# S7G7_footprint_simplified_w_ethernet_v1p.net
KiCad netlist of a schematic drawn in EAGLE
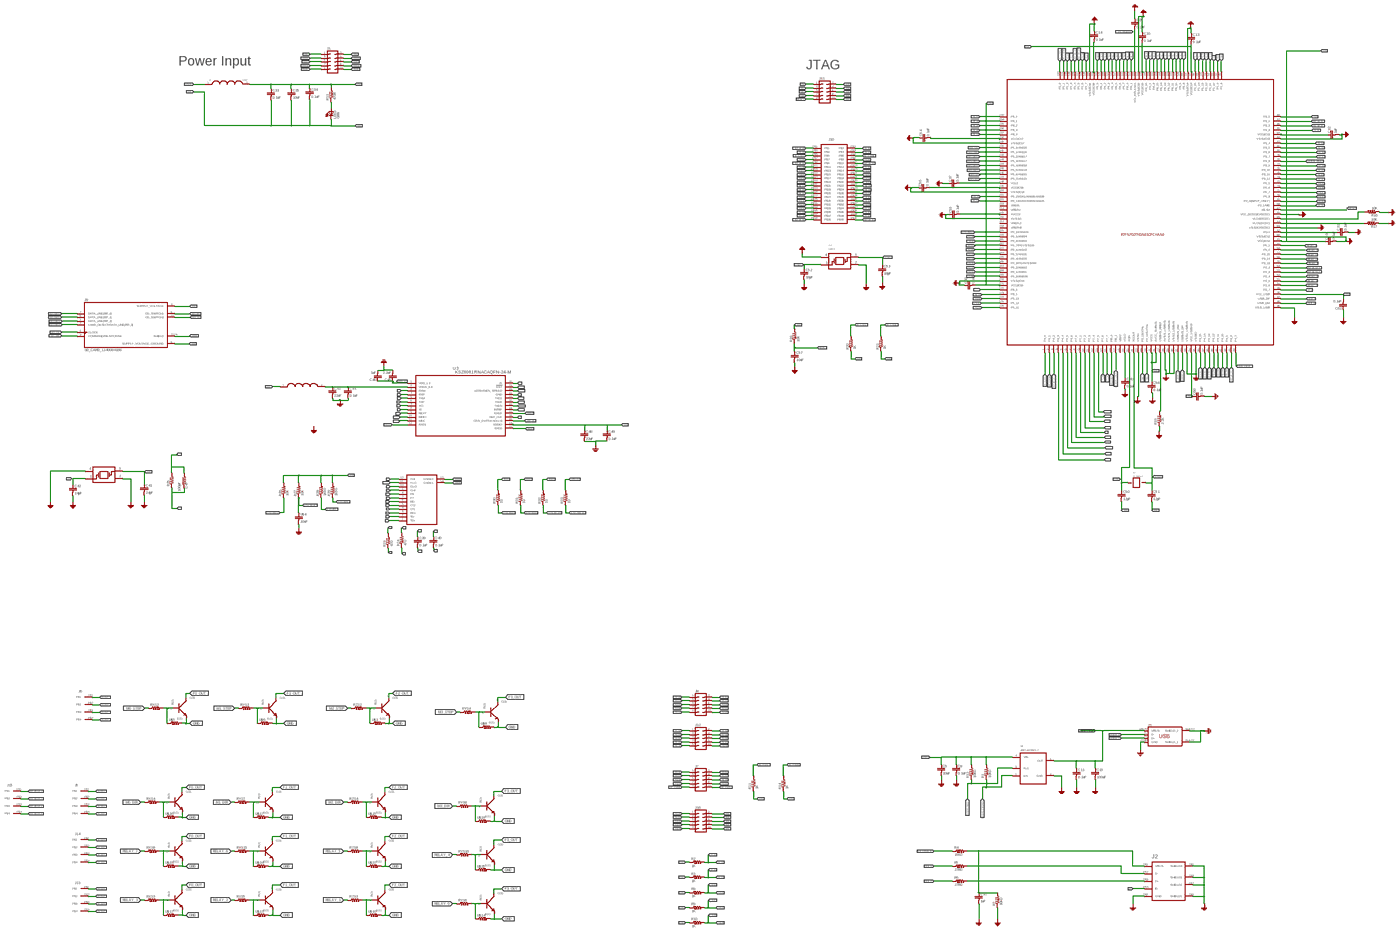
[diagram p0: schematic, sheet 1, overview]
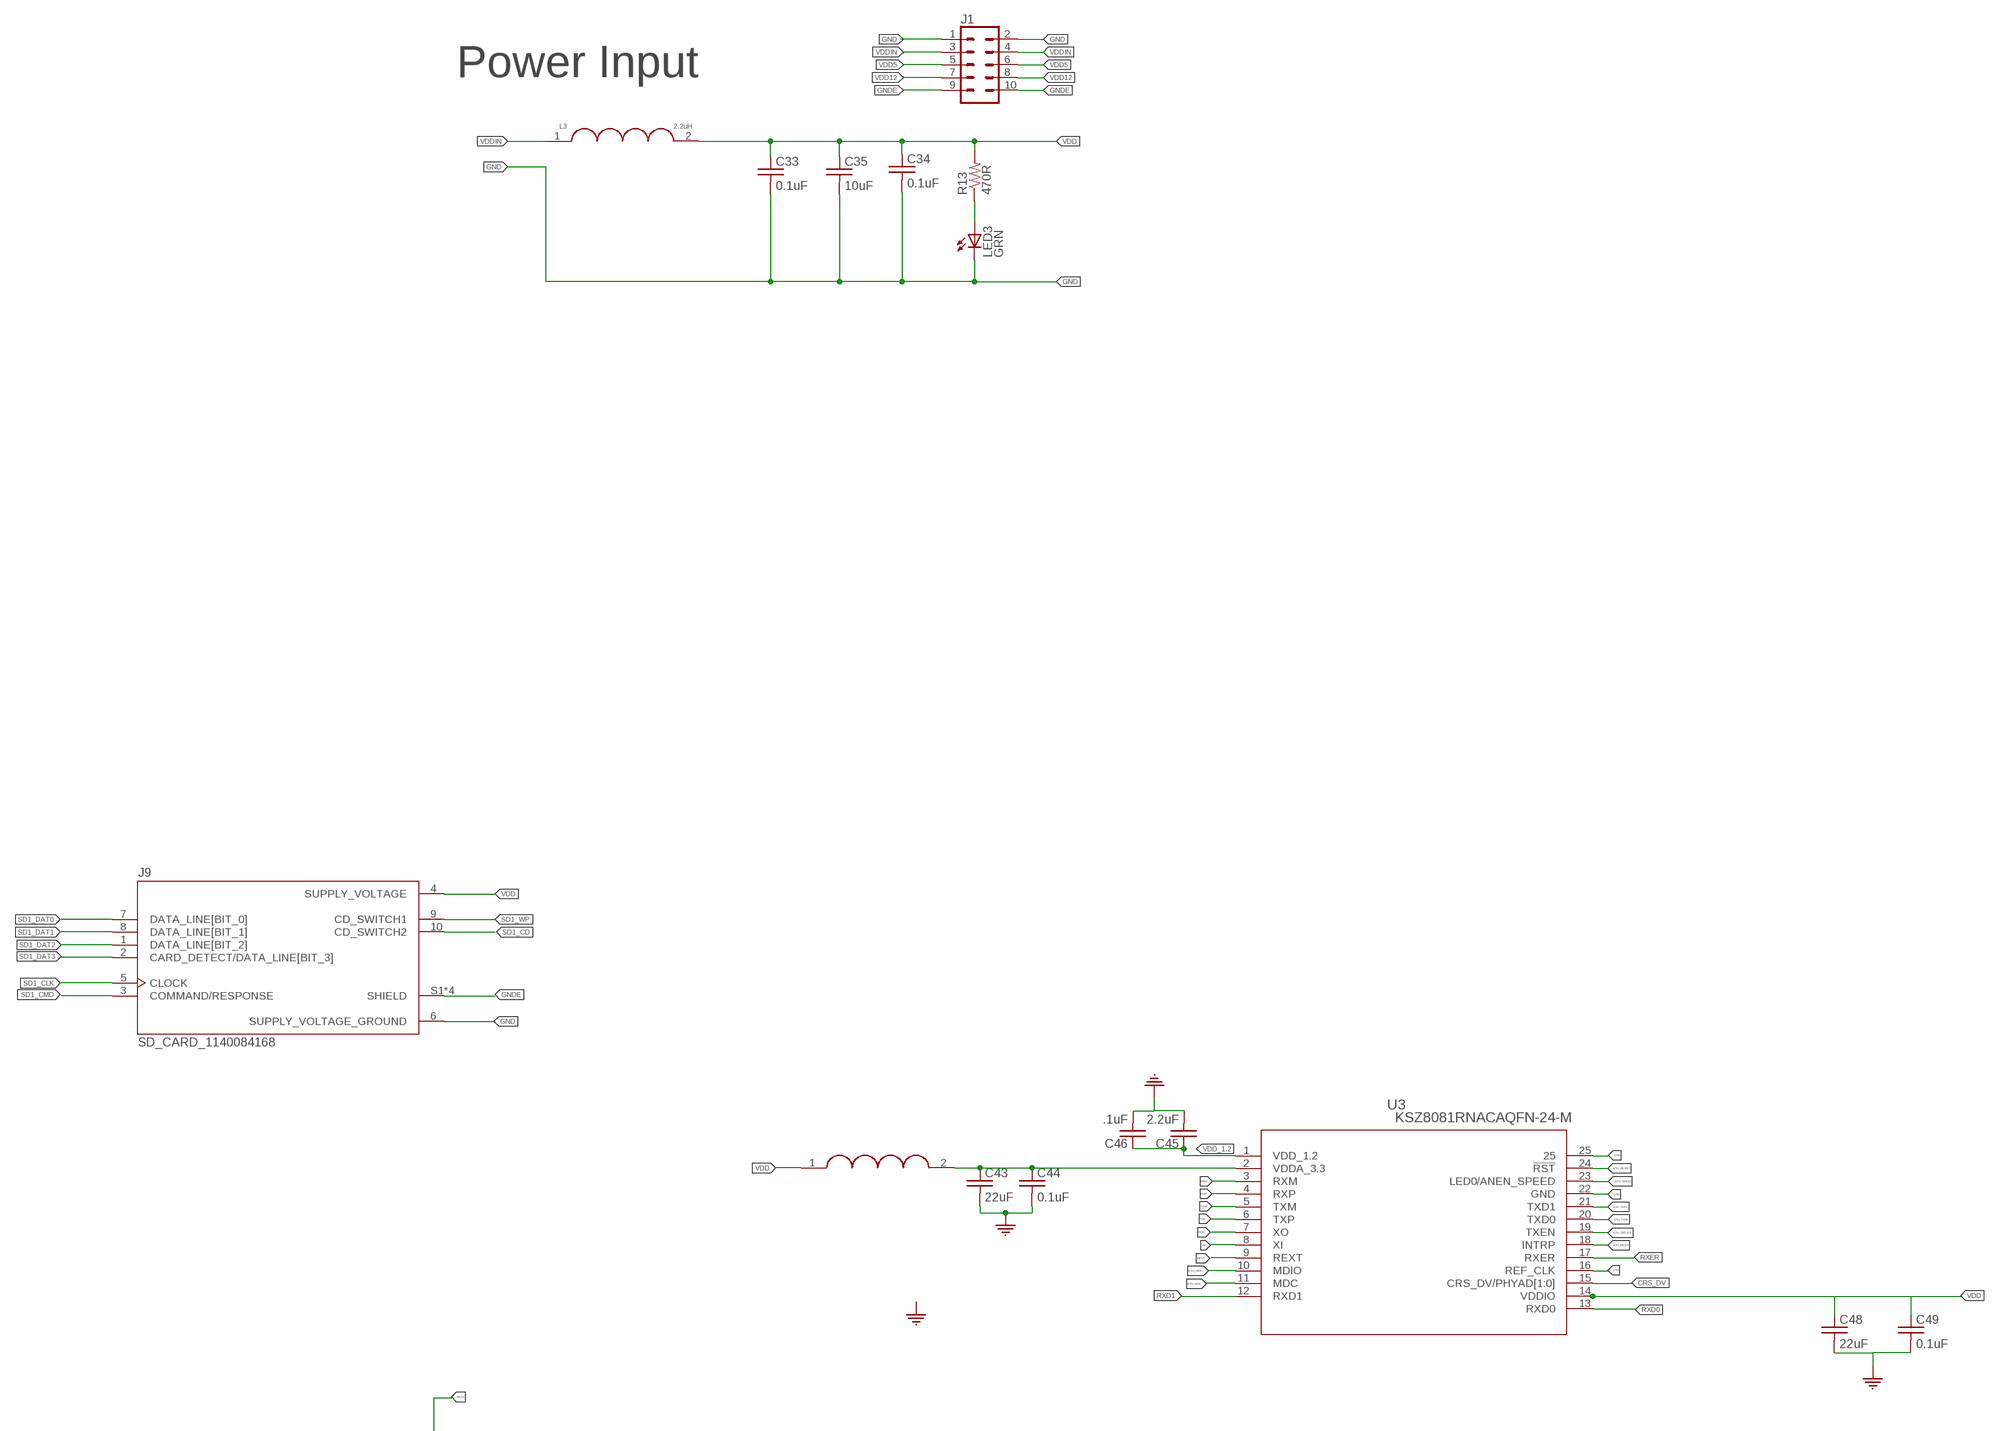
[diagram p1: schematic, sheet 1, part 1 of 4]
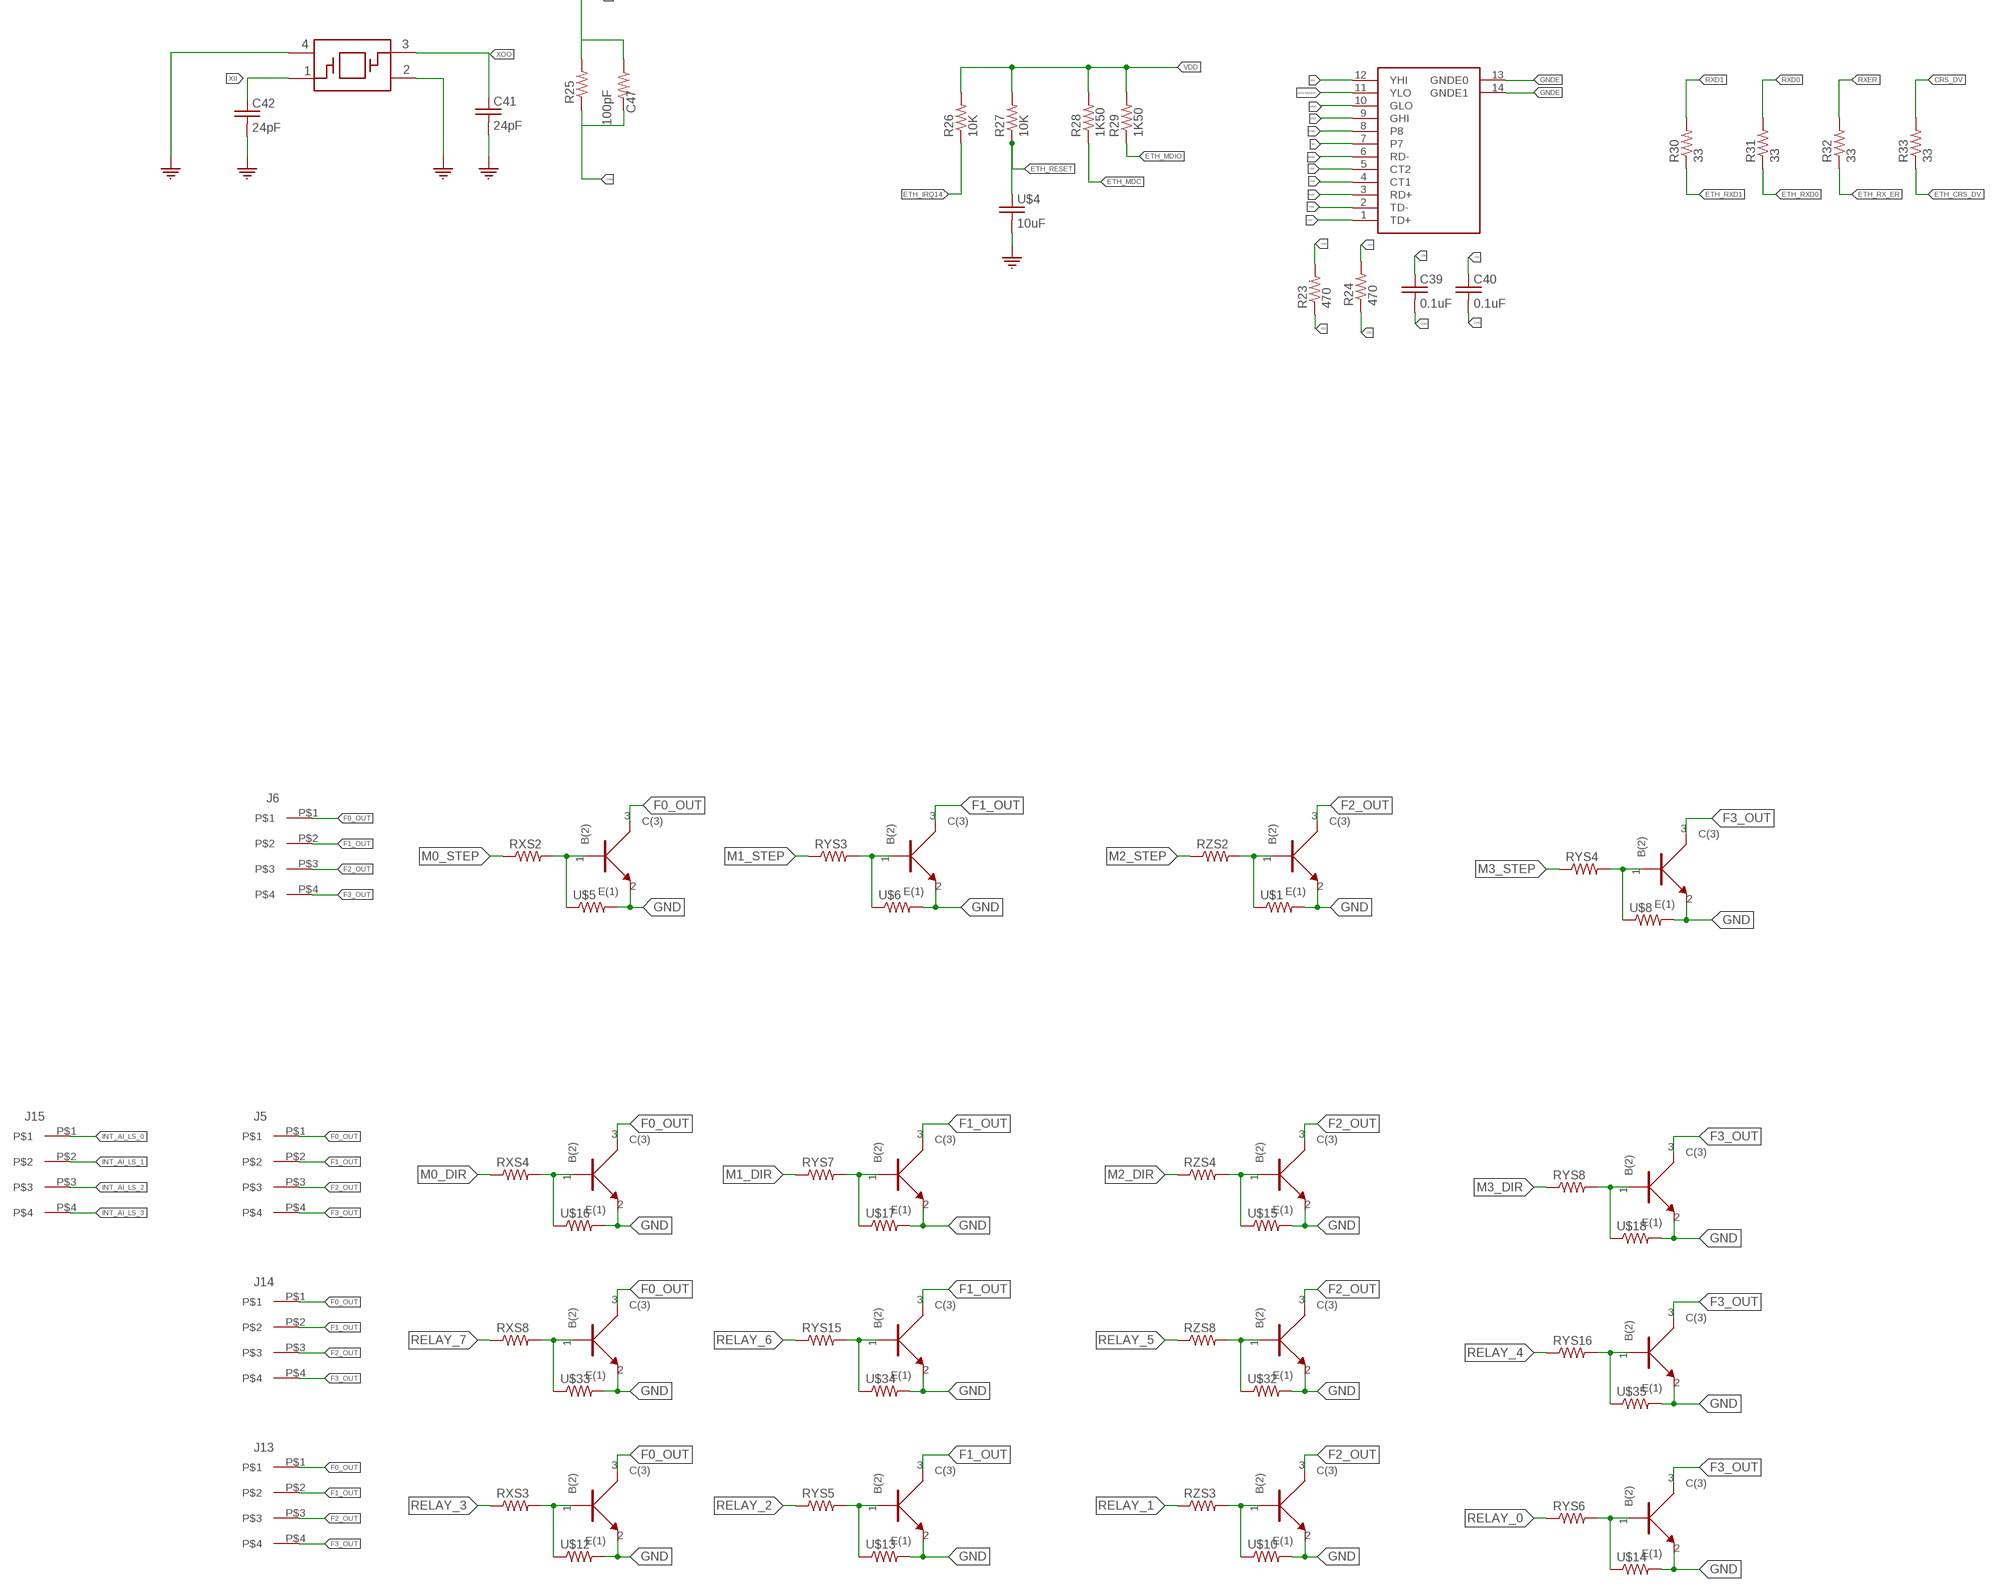
[diagram p2: schematic, sheet 1, part 2 of 4]
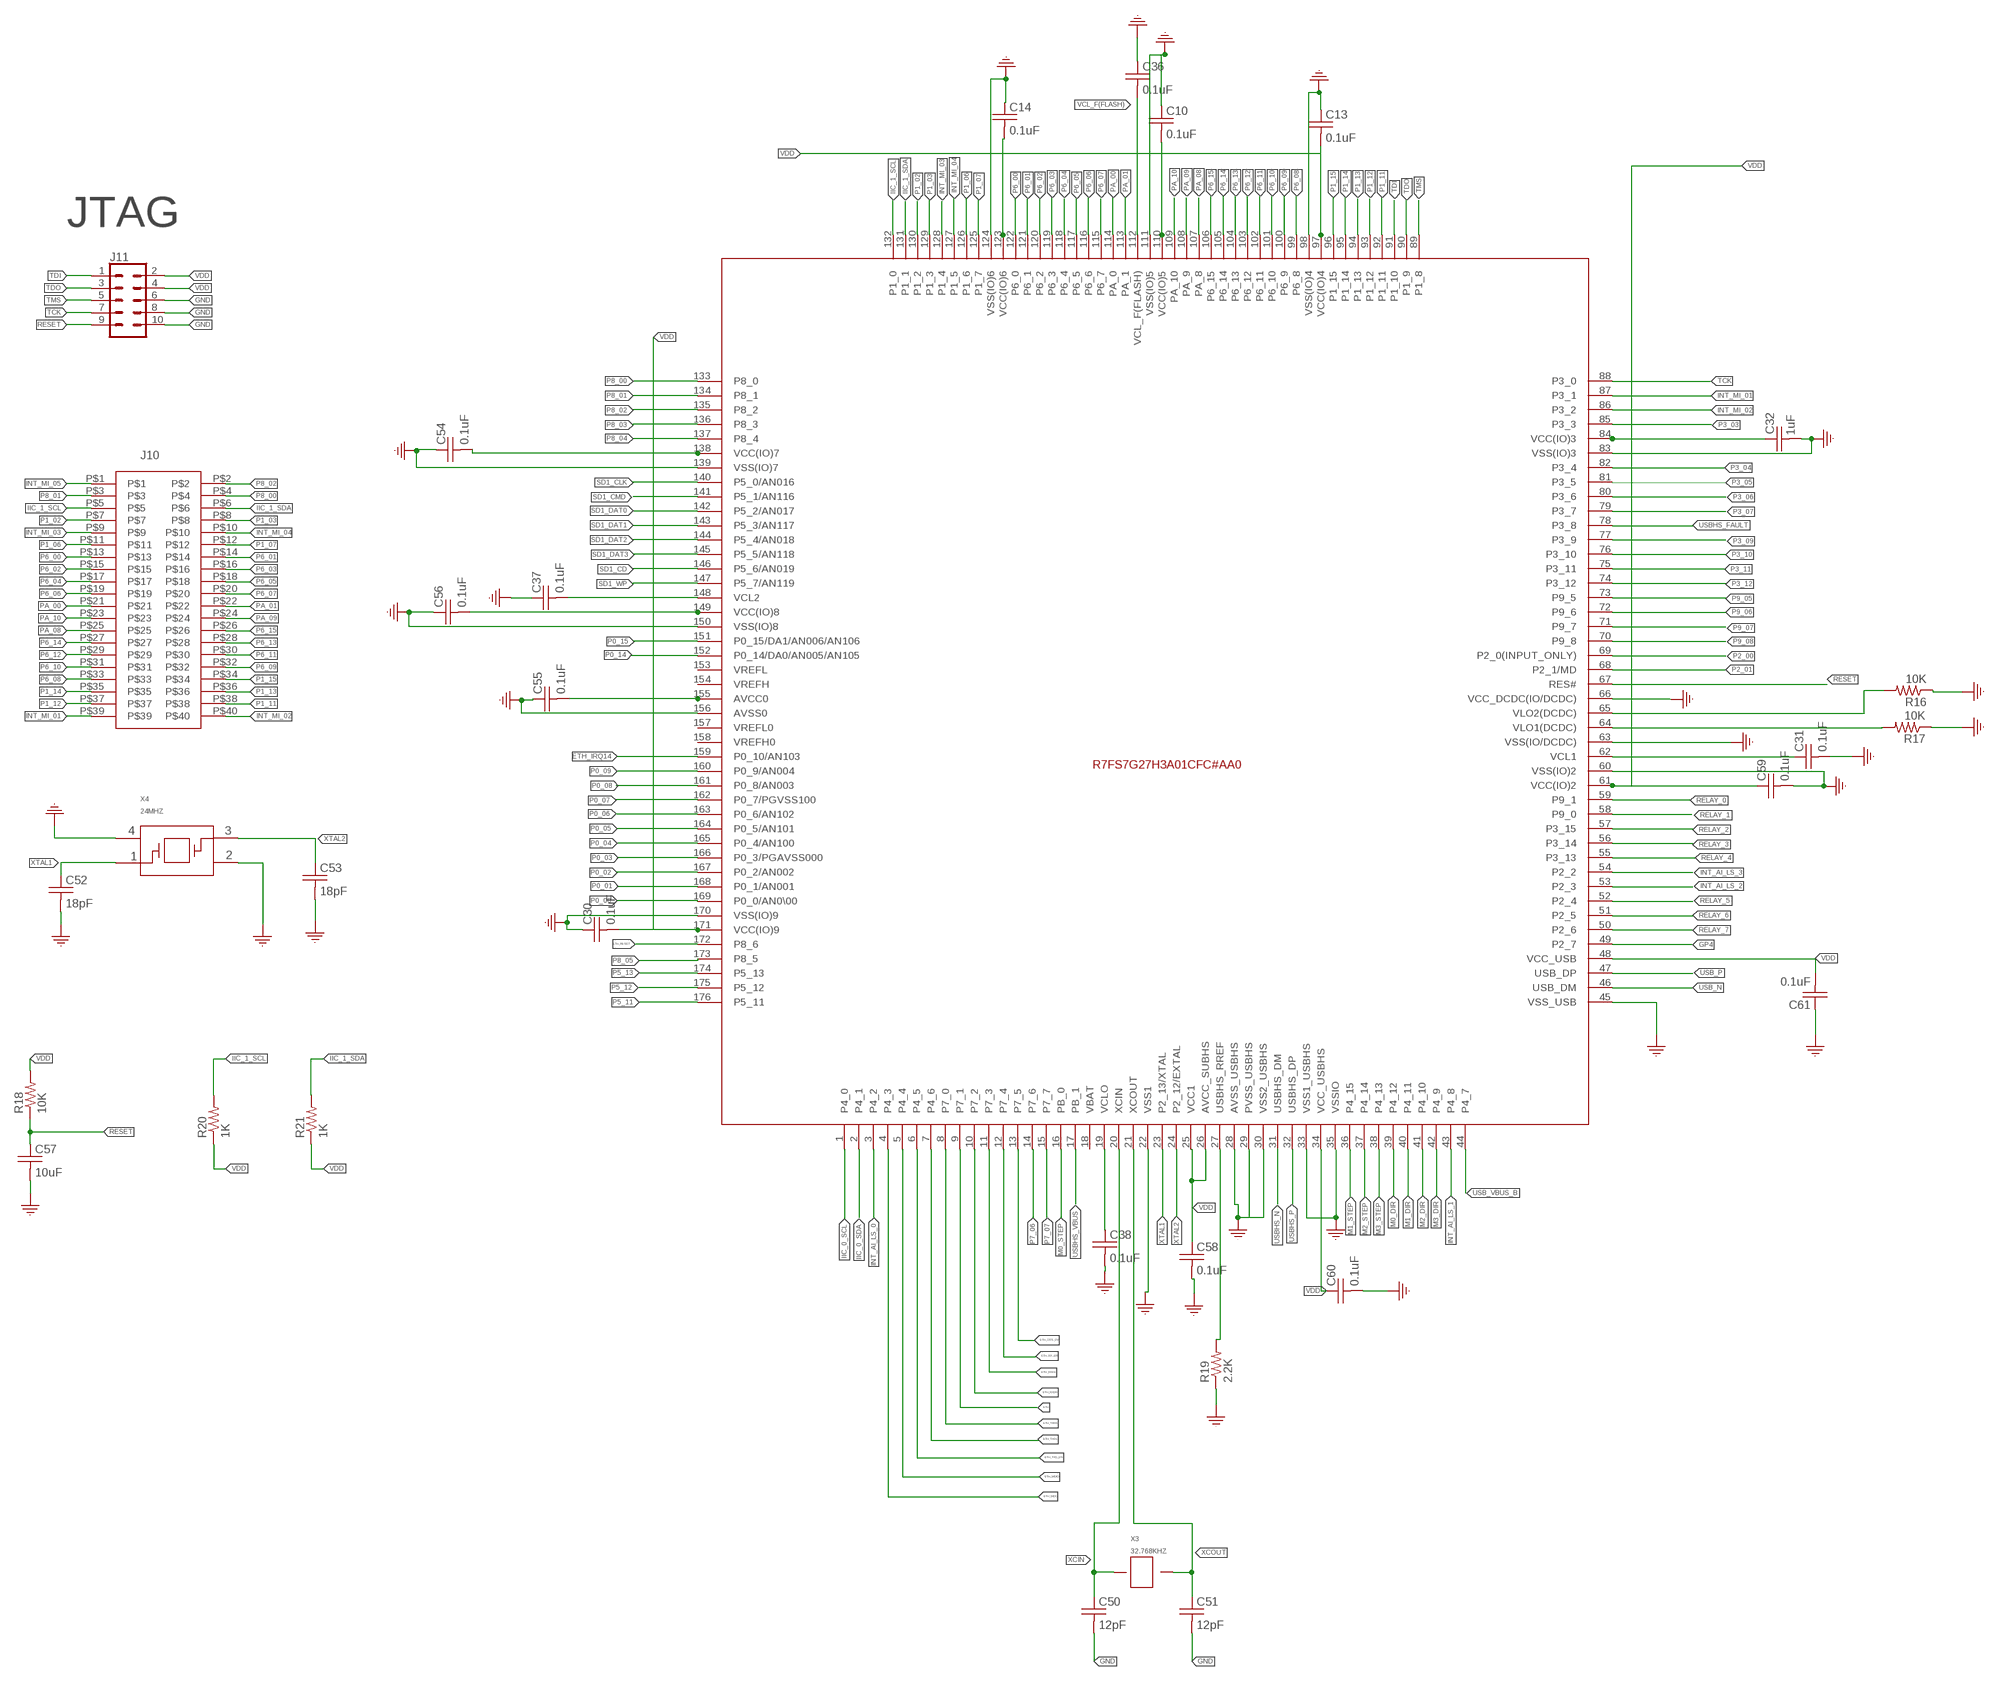
[diagram p3: schematic, sheet 1, part 3 of 4]
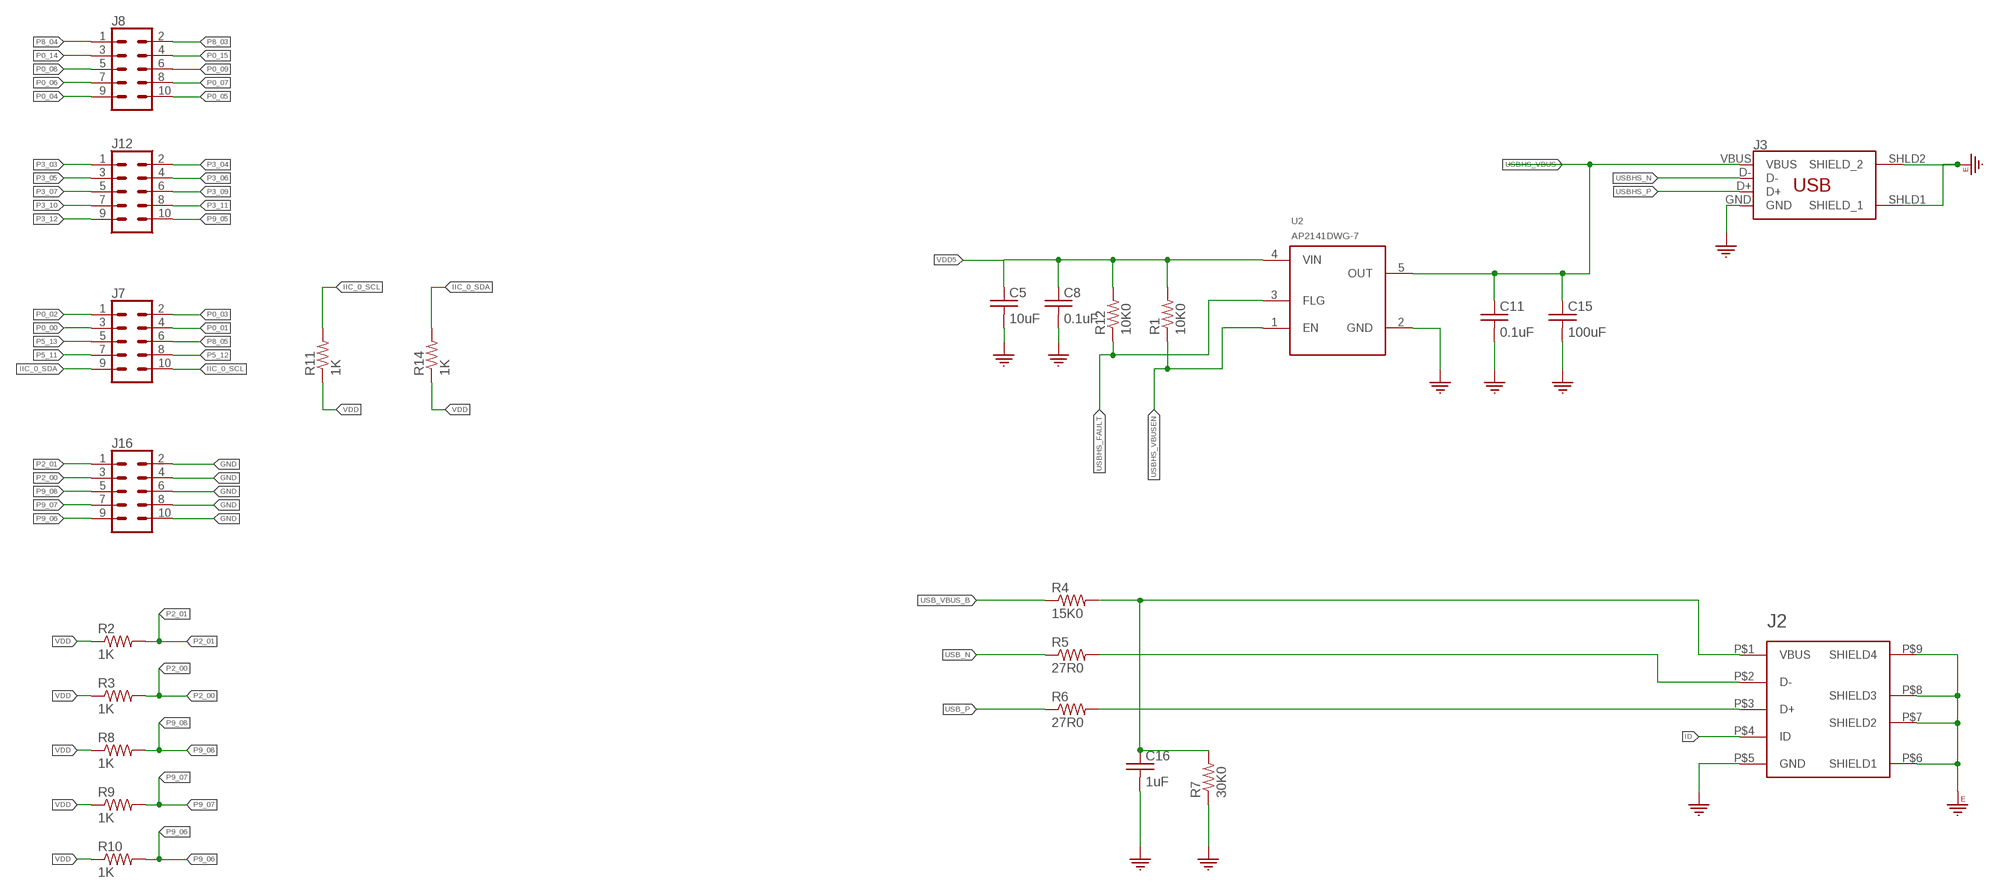
[diagram p4: schematic, sheet 1, part 4 of 4]

(export (version "E")
  (design (tool "Eeschema 10.0.6"))
  (components
    (comp (ref "C5")
      (value "10uF")
      (footprint "eagle-import:0402")
      (libsource (lib "eagle-import") (part "C_0402"))
    )
    (comp (ref "C8")
      (value "0.1uF")
      (footprint "eagle-import:0402")
      (libsource (lib "eagle-import") (part "C_0402"))
    )
    (comp (ref "C10")
      (value "0.1uF")
      (footprint "eagle-import:0402")
      (libsource (lib "eagle-import") (part "C_0402"))
    )
    (comp (ref "C11")
      (value "0.1uF")
      (footprint "eagle-import:0402")
      (libsource (lib "eagle-import") (part "C_0402"))
    )
    (comp (ref "C13")
      (value "0.1uF")
      (footprint "eagle-import:0402")
      (libsource (lib "eagle-import") (part "C_0402"))
    )
    (comp (ref "C14")
      (value "0.1uF")
      (footprint "eagle-import:0402")
      (libsource (lib "eagle-import") (part "C_0402"))
    )
    (comp (ref "C15")
      (value "100uF")
      (footprint "eagle-import:C1210")
      (libsource (lib "eagle-import") (part "C_1210"))
    )
    (comp (ref "C16")
      (value "1uF")
      (footprint "eagle-import:0402")
      (libsource (lib "eagle-import") (part "C_0402"))
    )
    (comp (ref "C30")
      (value "0.1uF")
      (footprint "eagle-import:0402")
      (libsource (lib "eagle-import") (part "C_0402"))
    )
    (comp (ref "C31")
      (value "0.1uF")
      (footprint "eagle-import:0402")
      (libsource (lib "eagle-import") (part "C_0402"))
    )
    (comp (ref "C32")
      (value "1uF")
      (footprint "eagle-import:0402")
      (libsource (lib "eagle-import") (part "C_0402"))
    )
    (comp (ref "C33")
      (value "0.1uF")
      (footprint "eagle-import:0402")
      (libsource (lib "eagle-import") (part "C_0402"))
    )
    (comp (ref "C34")
      (value "0.1uF")
      (footprint "eagle-import:0402")
      (libsource (lib "eagle-import") (part "C_0402"))
    )
    (comp (ref "C35")
      (value "10uF")
      (footprint "eagle-import:0402")
      (libsource (lib "eagle-import") (part "C_0402"))
    )
    (comp (ref "C36")
      (value "0.1uF")
      (footprint "eagle-import:0402")
      (libsource (lib "eagle-import") (part "C_0402"))
    )
    (comp (ref "C37")
      (value "0.1uF")
      (footprint "eagle-import:0402")
      (libsource (lib "eagle-import") (part "C_0402"))
    )
    (comp (ref "C38")
      (value "0.1uF")
      (footprint "eagle-import:0402")
      (libsource (lib "eagle-import") (part "C_0402"))
    )
    (comp (ref "C39")
      (value "0.1uF")
      (footprint "eagle-import:0402")
      (libsource (lib "eagle-import") (part "C_0402"))
    )
    (comp (ref "C40")
      (value "0.1uF")
      (footprint "eagle-import:0402")
      (libsource (lib "eagle-import") (part "C_0402"))
    )
    (comp (ref "C41")
      (value "24pF")
      (footprint "eagle-import:0402")
      (libsource (lib "eagle-import") (part "C_0402"))
    )
    (comp (ref "C42")
      (value "24pF")
      (footprint "eagle-import:0402")
      (libsource (lib "eagle-import") (part "C_0402"))
    )
    (comp (ref "C43")
      (value "22uF")
      (footprint "eagle-import:0603")
      (libsource (lib "eagle-import") (part "C_0603"))
    )
    (comp (ref "C44")
      (value "0.1uF")
      (footprint "eagle-import:0402")
      (libsource (lib "eagle-import") (part "C_0402"))
    )
    (comp (ref "C45")
      (value "2.2uF")
      (footprint "eagle-import:0402")
      (libsource (lib "eagle-import") (part "C_0402"))
    )
    (comp (ref "C46")
      (value ".1uF")
      (footprint "eagle-import:0402")
      (libsource (lib "eagle-import") (part "C_0402"))
    )
    (comp (ref "C47")
      (value "100pF")
      (footprint "eagle-import:0402")
      (libsource (lib "eagle-import") (part "R_0402"))
    )
    (comp (ref "C48")
      (value "22uF")
      (footprint "eagle-import:0603")
      (libsource (lib "eagle-import") (part "C_0603"))
    )
    (comp (ref "C49")
      (value "0.1uF")
      (footprint "eagle-import:0402")
      (libsource (lib "eagle-import") (part "C_0402"))
    )
    (comp (ref "C50")
      (value "12pF")
      (footprint "eagle-import:0402")
      (libsource (lib "eagle-import") (part "C_0402"))
    )
    (comp (ref "C51")
      (value "12pF")
      (footprint "eagle-import:0402")
      (libsource (lib "eagle-import") (part "C_0402"))
    )
    (comp (ref "C52")
      (value "18pF")
      (footprint "eagle-import:0402")
      (libsource (lib "eagle-import") (part "C_0402"))
    )
    (comp (ref "C53")
      (value "18pF")
      (footprint "eagle-import:0402")
      (libsource (lib "eagle-import") (part "C_0402"))
    )
    (comp (ref "C54")
      (value "0.1uF")
      (footprint "eagle-import:0402")
      (libsource (lib "eagle-import") (part "C_0402"))
    )
    (comp (ref "C55")
      (value "0.1uF")
      (footprint "eagle-import:0402")
      (libsource (lib "eagle-import") (part "C_0402"))
    )
    (comp (ref "C56")
      (value "0.1uF")
      (footprint "eagle-import:0402")
      (libsource (lib "eagle-import") (part "C_0402"))
    )
    (comp (ref "C57")
      (value "10uF")
      (footprint "eagle-import:0402")
      (libsource (lib "eagle-import") (part "C_0402"))
    )
    (comp (ref "C58")
      (value "0.1uF")
      (footprint "eagle-import:0402")
      (libsource (lib "eagle-import") (part "C_0402"))
    )
    (comp (ref "C59")
      (value "0.1uF")
      (footprint "eagle-import:0402")
      (libsource (lib "eagle-import") (part "C_0402"))
    )
    (comp (ref "C60")
      (value "0.1uF")
      (footprint "eagle-import:0402")
      (libsource (lib "eagle-import") (part "C_0402"))
    )
    (comp (ref "C61")
      (value "0.1uF")
      (footprint "eagle-import:0402")
      (libsource (lib "eagle-import") (part "C_0402"))
    )
    (comp (ref "FB2/2")
      (value "FB_0805_120_OHM")
      (footprint "eagle-import:0805")
      (libsource (lib "eagle-import") (part "FB_0805_120_OHM"))
    )
    (comp (ref "J1")
      (value "CONN_05X2PTH")
      (footprint "eagle-import:2X5")
      (libsource (lib "eagle-import") (part "CONN_05X2PTH"))
    )
    (comp (ref "J2")
      (value "USB_MICRO-B")
      (footprint "eagle-import:USB_MICRO-B")
      (libsource (lib "eagle-import") (part "USB_MICRO-B"))
    )
    (comp (ref "J3")
      (value "USB_A")
      (footprint "eagle-import:USB_A_SMT")
      (libsource (lib "eagle-import") (part "USB_A"))
    )
    (comp (ref "J4")
      (value "RJ45_WITH_ELEC")
      (footprint "eagle-import:RJ45_TH_ELEC")
      (libsource (lib "eagle-import") (part "RJ45_WITH_ELEC"))
    )
    (comp (ref "J5")
      (value "3.81MM_1_X_4_RT_ANGLE_PLUG_HEADER")
      (footprint "eagle-import:1X4_3.81MM_PITCH")
      (libsource (lib "eagle-import") (part "3.81MM_1_X_4_RT_ANGLE_PLUG_HEADER"))
    )
    (comp (ref "J6")
      (value "3.81MM_1_X_4_RT_ANGLE_PLUG_HEADER")
      (footprint "eagle-import:1X4_3.81MM_PITCH")
      (libsource (lib "eagle-import") (part "3.81MM_1_X_4_RT_ANGLE_PLUG_HEADER"))
    )
    (comp (ref "J7")
      (value "CONN_05X2NO_SILK")
      (footprint "eagle-import:2X5_NOSILK")
      (libsource (lib "eagle-import") (part "CONN_05X2NO_SILK"))
    )
    (comp (ref "J8")
      (value "CONN_05X2NO_SILK")
      (footprint "eagle-import:2X5_NOSILK")
      (libsource (lib "eagle-import") (part "CONN_05X2NO_SILK"))
    )
    (comp (ref "J9")
      (value "SD_CARD_1140084168")
      (footprint "eagle-import:AMPHENOL_1140084168")
      (fields
        (field (name "DIGI-KEY_PART_NUMBER") "114-00841-68-1-ND")
        (field (name "MF") "Amphenol ICC")
        (field (name "MP") "114-00841-68")
      )
      (libsource (lib "eagle-import") (part "SD_CARD_1140084168"))
    )
    (comp (ref "J10")
      (value "HEADER_2_X_20_GENERIC")
      (footprint "eagle-import:HEADER_2_X_20_.1_INCH")
      (libsource (lib "eagle-import") (part "HEADER_2_X_20_GENERIC"))
    )
    (comp (ref "J11")
      (value "CONN_05X2PTH")
      (footprint "eagle-import:2X5")
      (libsource (lib "eagle-import") (part "CONN_05X2PTH"))
    )
    (comp (ref "J12")
      (value "CONN_05X2NO_SILK")
      (footprint "eagle-import:2X5_NOSILK")
      (libsource (lib "eagle-import") (part "CONN_05X2NO_SILK"))
    )
    (comp (ref "J13")
      (value "3.81MM_1_X_4_RT_ANGLE_PLUG_HEADER")
      (footprint "eagle-import:1X4_3.81MM_PITCH")
      (libsource (lib "eagle-import") (part "3.81MM_1_X_4_RT_ANGLE_PLUG_HEADER"))
    )
    (comp (ref "J14")
      (value "3.81MM_1_X_4_RT_ANGLE_PLUG_HEADER")
      (footprint "eagle-import:1X4_3.81MM_PITCH")
      (libsource (lib "eagle-import") (part "3.81MM_1_X_4_RT_ANGLE_PLUG_HEADER"))
    )
    (comp (ref "J15")
      (value "3.81MM_1_X_4_RT_ANGLE_PLUG_HEADER")
      (footprint "eagle-import:1X4_3.81MM_PITCH")
      (libsource (lib "eagle-import") (part "3.81MM_1_X_4_RT_ANGLE_PLUG_HEADER"))
    )
    (comp (ref "J16")
      (value "CONN_05X2SHD_SMD")
      (footprint "eagle-import:2X5-SHROUDED_SMD")
      (libsource (lib "eagle-import") (part "CONN_05X2SHD_SMD"))
    )
    (comp (ref "L3")
      (value "2.2uH")
      (footprint "eagle-import:1008_(2520_METRIC)")
      (libsource (lib "eagle-import") (part "INDUCTOR_1008_2.2_MH_1.3A"))
    )
    (comp (ref "LED3")
      (value "LED_0805_GREEN")
      (footprint "eagle-import:LED_0805_GREEN")
      (libsource (lib "eagle-import") (part "LED_0805_GREEN"))
    )
    (comp (ref "R1")
      (value "10K0")
      (footprint "eagle-import:0402")
      (libsource (lib "eagle-import") (part "R_0402"))
    )
    (comp (ref "R2")
      (value "1K")
      (footprint "eagle-import:0402")
      (libsource (lib "eagle-import") (part "R_0402"))
    )
    (comp (ref "R3")
      (value "1K")
      (footprint "eagle-import:0402")
      (libsource (lib "eagle-import") (part "R_0402"))
    )
    (comp (ref "R4")
      (value "15K0")
      (footprint "eagle-import:0402")
      (libsource (lib "eagle-import") (part "R_0402"))
    )
    (comp (ref "R5")
      (value "27R0")
      (footprint "eagle-import:0402")
      (libsource (lib "eagle-import") (part "R_0402"))
    )
    (comp (ref "R6")
      (value "27R0")
      (footprint "eagle-import:0402")
      (libsource (lib "eagle-import") (part "R_0402"))
    )
    (comp (ref "R7")
      (value "30K0")
      (footprint "eagle-import:0402")
      (libsource (lib "eagle-import") (part "R_0402"))
    )
    (comp (ref "R8")
      (value "1K")
      (footprint "eagle-import:0402")
      (libsource (lib "eagle-import") (part "R_0402"))
    )
    (comp (ref "R9")
      (value "1K")
      (footprint "eagle-import:0402")
      (libsource (lib "eagle-import") (part "R_0402"))
    )
    (comp (ref "R10")
      (value "1K")
      (footprint "eagle-import:0402")
      (libsource (lib "eagle-import") (part "R_0402"))
    )
    (comp (ref "R11")
      (value "1K")
      (footprint "eagle-import:0402")
      (libsource (lib "eagle-import") (part "R_0402"))
    )
    (comp (ref "R12")
      (value "10K0")
      (footprint "eagle-import:0402")
      (libsource (lib "eagle-import") (part "R_0402"))
    )
    (comp (ref "R13")
      (value "470R")
      (footprint "eagle-import:0402")
      (libsource (lib "eagle-import") (part "R_0402"))
    )
    (comp (ref "R14")
      (value "1K")
      (footprint "eagle-import:0402")
      (libsource (lib "eagle-import") (part "R_0402"))
    )
    (comp (ref "R16")
      (value "10K")
      (footprint "eagle-import:0402")
      (libsource (lib "eagle-import") (part "R_0402"))
    )
    (comp (ref "R17")
      (value "10K")
      (footprint "eagle-import:0402")
      (libsource (lib "eagle-import") (part "R_0402"))
    )
    (comp (ref "R18")
      (value "10K")
      (footprint "eagle-import:0402")
      (libsource (lib "eagle-import") (part "R_0402"))
    )
    (comp (ref "R19")
      (value "2.2K")
      (footprint "eagle-import:0402")
      (libsource (lib "eagle-import") (part "R_0402"))
    )
    (comp (ref "R20")
      (value "1K")
      (footprint "eagle-import:0402")
      (libsource (lib "eagle-import") (part "R_0402"))
    )
    (comp (ref "R21")
      (value "1K")
      (footprint "eagle-import:0402")
      (libsource (lib "eagle-import") (part "R_0402"))
    )
    (comp (ref "R23")
      (value "470")
      (footprint "eagle-import:0402")
      (libsource (lib "eagle-import") (part "R_0402"))
    )
    (comp (ref "R24")
      (value "470")
      (footprint "eagle-import:0402")
      (libsource (lib "eagle-import") (part "R_0402"))
    )
    (comp (ref "R25")
      (value "6k49")
      (footprint "eagle-import:0402")
      (libsource (lib "eagle-import") (part "R_0402"))
    )
    (comp (ref "R26")
      (value "10K")
      (footprint "eagle-import:0402")
      (libsource (lib "eagle-import") (part "R_0402"))
    )
    (comp (ref "R27")
      (value "10K")
      (footprint "eagle-import:0402")
      (libsource (lib "eagle-import") (part "R_0402"))
    )
    (comp (ref "R28")
      (value "1K50")
      (footprint "eagle-import:0402")
      (libsource (lib "eagle-import") (part "R_0402"))
    )
    (comp (ref "R29")
      (value "1K50")
      (footprint "eagle-import:0402")
      (libsource (lib "eagle-import") (part "R_0402"))
    )
    (comp (ref "R30")
      (value "33")
      (footprint "eagle-import:0402")
      (libsource (lib "eagle-import") (part "R_0402"))
    )
    (comp (ref "R31")
      (value "33")
      (footprint "eagle-import:0402")
      (libsource (lib "eagle-import") (part "R_0402"))
    )
    (comp (ref "R32")
      (value "33")
      (footprint "eagle-import:0402")
      (libsource (lib "eagle-import") (part "R_0402"))
    )
    (comp (ref "R33")
      (value "33")
      (footprint "eagle-import:0402")
      (libsource (lib "eagle-import") (part "R_0402"))
    )
    (comp (ref "RXS2")
      (value "1K")
      (footprint "eagle-import:0402")
      (libsource (lib "eagle-import") (part "R_0402"))
    )
    (comp (ref "RXS3")
      (value "1K")
      (footprint "eagle-import:0402")
      (libsource (lib "eagle-import") (part "R_0402"))
    )
    (comp (ref "RXS4")
      (value "1K")
      (footprint "eagle-import:0402")
      (libsource (lib "eagle-import") (part "R_0402"))
    )
    (comp (ref "RXS8")
      (value "1K")
      (footprint "eagle-import:0402")
      (libsource (lib "eagle-import") (part "R_0402"))
    )
    (comp (ref "RYS3")
      (value "1K")
      (footprint "eagle-import:0402")
      (libsource (lib "eagle-import") (part "R_0402"))
    )
    (comp (ref "RYS4")
      (value "1K")
      (footprint "eagle-import:0402")
      (libsource (lib "eagle-import") (part "R_0402"))
    )
    (comp (ref "RYS5")
      (value "1K")
      (footprint "eagle-import:0402")
      (libsource (lib "eagle-import") (part "R_0402"))
    )
    (comp (ref "RYS6")
      (value "1K")
      (footprint "eagle-import:0402")
      (libsource (lib "eagle-import") (part "R_0402"))
    )
    (comp (ref "RYS7")
      (value "1K")
      (footprint "eagle-import:0402")
      (libsource (lib "eagle-import") (part "R_0402"))
    )
    (comp (ref "RYS8")
      (value "1K")
      (footprint "eagle-import:0402")
      (libsource (lib "eagle-import") (part "R_0402"))
    )
    (comp (ref "RYS15")
      (value "1K")
      (footprint "eagle-import:0402")
      (libsource (lib "eagle-import") (part "R_0402"))
    )
    (comp (ref "RYS16")
      (value "1K")
      (footprint "eagle-import:0402")
      (libsource (lib "eagle-import") (part "R_0402"))
    )
    (comp (ref "RZS2")
      (value "1K")
      (footprint "eagle-import:0402")
      (libsource (lib "eagle-import") (part "R_0402"))
    )
    (comp (ref "RZS3")
      (value "1K")
      (footprint "eagle-import:0402")
      (libsource (lib "eagle-import") (part "R_0402"))
    )
    (comp (ref "RZS4")
      (value "1K")
      (footprint "eagle-import:0402")
      (libsource (lib "eagle-import") (part "R_0402"))
    )
    (comp (ref "RZS8")
      (value "1K")
      (footprint "eagle-import:0402")
      (libsource (lib "eagle-import") (part "R_0402"))
    )
    (comp (ref "U$1")
      (value "1K")
      (footprint "eagle-import:0402")
      (libsource (lib "eagle-import") (part "R_0402"))
    )
    (comp (ref "U$3")
      (value "XTAL_25_MHZ")
      (footprint "eagle-import:SMD_3225")
      (libsource (lib "eagle-import") (part "XTAL_25_MHZ"))
    )
    (comp (ref "U$4")
      (value "10uF")
      (footprint "eagle-import:0402")
      (libsource (lib "eagle-import") (part "C_0402"))
    )
    (comp (ref "U$5")
      (value "1K")
      (footprint "eagle-import:0402")
      (libsource (lib "eagle-import") (part "R_0402"))
    )
    (comp (ref "U$6")
      (value "1K")
      (footprint "eagle-import:0402")
      (libsource (lib "eagle-import") (part "R_0402"))
    )
    (comp (ref "U$8")
      (value "1K")
      (footprint "eagle-import:0402")
      (libsource (lib "eagle-import") (part "R_0402"))
    )
    (comp (ref "U$10")
      (value "1K")
      (footprint "eagle-import:0402")
      (libsource (lib "eagle-import") (part "R_0402"))
    )
    (comp (ref "U$12")
      (value "1K")
      (footprint "eagle-import:0402")
      (libsource (lib "eagle-import") (part "R_0402"))
    )
    (comp (ref "U$13")
      (value "1K")
      (footprint "eagle-import:0402")
      (libsource (lib "eagle-import") (part "R_0402"))
    )
    (comp (ref "U$14")
      (value "1K")
      (footprint "eagle-import:0402")
      (libsource (lib "eagle-import") (part "R_0402"))
    )
    (comp (ref "U$15")
      (value "1K")
      (footprint "eagle-import:0402")
      (libsource (lib "eagle-import") (part "R_0402"))
    )
    (comp (ref "U$16")
      (value "1K")
      (footprint "eagle-import:0402")
      (libsource (lib "eagle-import") (part "R_0402"))
    )
    (comp (ref "U$17")
      (value "1K")
      (footprint "eagle-import:0402")
      (libsource (lib "eagle-import") (part "R_0402"))
    )
    (comp (ref "U$18")
      (value "1K")
      (footprint "eagle-import:0402")
      (libsource (lib "eagle-import") (part "R_0402"))
    )
    (comp (ref "U$32")
      (value "1K")
      (footprint "eagle-import:0402")
      (libsource (lib "eagle-import") (part "R_0402"))
    )
    (comp (ref "U$33")
      (value "1K")
      (footprint "eagle-import:0402")
      (libsource (lib "eagle-import") (part "R_0402"))
    )
    (comp (ref "U$34")
      (value "1K")
      (footprint "eagle-import:0402")
      (libsource (lib "eagle-import") (part "R_0402"))
    )
    (comp (ref "U$35")
      (value "1K")
      (footprint "eagle-import:0402")
      (libsource (lib "eagle-import") (part "R_0402"))
    )
    (comp (ref "U2")
      (value "AP2141DWG-5")
      (footprint "eagle-import:SOT-23-5")
      (libsource (lib "eagle-import") (part "AP2141DWG-5"))
    )
    (comp (ref "U3")
      (value "KSZ8081RNACAQFN-24-M")
      (footprint "eagle-import:QFN-24-M")
      (fields (field (name "MANUFACTURER_PART_NUMBER") "KSZ8081RNACA"))
      (libsource (lib "eagle-import") (part "KSZ8081RNACAQFN-24-M"))
    )
    (comp (ref "U4")
      (value "S7G2_X_176")
      (footprint "eagle-import:LQFP176_24X24")
      (libsource (lib "eagle-import") (part "S7G2_X_176"))
    )
    (comp (ref "U7")
      (value "BC846BW")
      (footprint "eagle-import:SOT323")
      (libsource (lib "eagle-import") (part "BC846BW"))
    )
    (comp (ref "U8")
      (value "BC846BW")
      (footprint "eagle-import:SOT323")
      (libsource (lib "eagle-import") (part "BC846BW"))
    )
    (comp (ref "U9")
      (value "BC846BW")
      (footprint "eagle-import:SOT323")
      (libsource (lib "eagle-import") (part "BC846BW"))
    )
    (comp (ref "U10")
      (value "BC846BW")
      (footprint "eagle-import:SOT323")
      (libsource (lib "eagle-import") (part "BC846BW"))
    )
    (comp (ref "U12")
      (value "BC846BW")
      (footprint "eagle-import:SOT323")
      (libsource (lib "eagle-import") (part "BC846BW"))
    )
    (comp (ref "U13")
      (value "BC846BW")
      (footprint "eagle-import:SOT323")
      (libsource (lib "eagle-import") (part "BC846BW"))
    )
    (comp (ref "U14")
      (value "BC846BW")
      (footprint "eagle-import:SOT323")
      (libsource (lib "eagle-import") (part "BC846BW"))
    )
    (comp (ref "U15")
      (value "BC846BW")
      (footprint "eagle-import:SOT323")
      (libsource (lib "eagle-import") (part "BC846BW"))
    )
    (comp (ref "U16")
      (value "BC846BW")
      (footprint "eagle-import:SOT323")
      (libsource (lib "eagle-import") (part "BC846BW"))
    )
    (comp (ref "U17")
      (value "BC846BW")
      (footprint "eagle-import:SOT323")
      (libsource (lib "eagle-import") (part "BC846BW"))
    )
    (comp (ref "U18")
      (value "BC846BW")
      (footprint "eagle-import:SOT323")
      (libsource (lib "eagle-import") (part "BC846BW"))
    )
    (comp (ref "U19")
      (value "BC846BW")
      (footprint "eagle-import:SOT323")
      (libsource (lib "eagle-import") (part "BC846BW"))
    )
    (comp (ref "U32")
      (value "BC846BW")
      (footprint "eagle-import:SOT323")
      (libsource (lib "eagle-import") (part "BC846BW"))
    )
    (comp (ref "U33")
      (value "BC846BW")
      (footprint "eagle-import:SOT323")
      (libsource (lib "eagle-import") (part "BC846BW"))
    )
    (comp (ref "U34")
      (value "BC846BW")
      (footprint "eagle-import:SOT323")
      (libsource (lib "eagle-import") (part "BC846BW"))
    )
    (comp (ref "U35")
      (value "BC846BW")
      (footprint "eagle-import:SOT323")
      (libsource (lib "eagle-import") (part "BC846BW"))
    )
    (comp (ref "X3")
      (value "32.768KHZ")
      (footprint "eagle-import:SMD_X_2_PADS")
      (libsource (lib "eagle-import") (part "XTAL_32.768KHZ"))
    )
    (comp (ref "X4")
      (value "24MHZ")
      (footprint "eagle-import:SMD_3225")
      (libsource (lib "eagle-import") (part "XTAL_24_MHZ"))
    )
  )
  (nets
    (net (code "1") (name "C58") (class "Default")
      (node (ref "C39") (pin "P$1") (pinfunction "1_P$1") (pintype "passive"))
      (node (ref "J4") (pin "4") (pinfunction "CT1_4") (pintype "bidirectional"))
    )
    (net (code "2") (name "C60") (class "Default")
      (node (ref "C40") (pin "P$1") (pinfunction "1_P$1") (pintype "passive"))
      (node (ref "J4") (pin "5") (pinfunction "CT2_5") (pintype "bidirectional"))
    )
    (net (code "3") (name "CRS_DV") (class "Default")
      (node (ref "R33") (pin "P$2") (pinfunction "2_P$2") (pintype "passive"))
      (node (ref "U3") (pin "15") (pinfunction "CRS_DV/PHYAD[1:0]_15") (pintype "bidirectional"))
    )
    (net (code "4") (name "ETH") (class "Default")
      (node (ref "U3") (pin "16") (pinfunction "REF_CLK_16") (pintype "bidirectional"))
      (node (ref "U4") (pin "9") (pinfunction "P7_1_9") (pintype "bidirectional"))
    )
    (net (code "5") (name "ETH_CRS_DV") (class "Default")
      (node (ref "R33") (pin "P$1") (pinfunction "1_P$1") (pintype "passive"))
      (node (ref "U4") (pin "13") (pinfunction "P7_5_13") (pintype "bidirectional"))
    )
    (net (code "6") (name "ETH_IRQ14") (class "Default")
      (node (ref "R26") (pin "P$1") (pinfunction "1_P$1") (pintype "passive"))
      (node (ref "U3") (pin "18") (pinfunction "INTRP_18") (pintype "bidirectional"))
      (node (ref "U4") (pin "159") (pinfunction "P0_10/AN103_159") (pintype "bidirectional"))
    )
    (net (code "7") (name "ETH_MDC") (class "Default")
      (node (ref "R28") (pin "P$1") (pinfunction "1_P$1") (pintype "passive"))
      (node (ref "U3") (pin "11") (pinfunction "MDC_11") (pintype "input"))
      (node (ref "U4") (pin "4") (pinfunction "P4_3_4") (pintype "bidirectional"))
    )
    (net (code "8") (name "ETH_MDIO") (class "Default")
      (node (ref "R29") (pin "P$1") (pinfunction "1_P$1") (pintype "passive"))
      (node (ref "U3") (pin "10") (pinfunction "MDIO_10") (pintype "bidirectional"))
      (node (ref "U4") (pin "5") (pinfunction "P4_4_5") (pintype "bidirectional"))
    )
    (net (code "9") (name "ETH_RESET") (class "Default")
      (node (ref "R27") (pin "P$1") (pinfunction "1_P$1") (pintype "passive"))
      (node (ref "U$4") (pin "P$1") (pinfunction "1_P$1") (pintype "passive"))
      (node (ref "U3") (pin "24") (pinfunction "~{RST}_24") (pintype "input"))
      (node (ref "U4") (pin "172") (pinfunction "P8_6_172") (pintype "bidirectional"))
    )
    (net (code "10") (name "ETH_RXD0") (class "Default")
      (node (ref "R31") (pin "P$1") (pinfunction "1_P$1") (pintype "passive"))
      (node (ref "U4") (pin "10") (pinfunction "P7_2_10") (pintype "bidirectional"))
    )
    (net (code "11") (name "ETH_RXD1") (class "Default")
      (node (ref "R30") (pin "P$1") (pinfunction "1_P$1") (pintype "passive"))
      (node (ref "U4") (pin "11") (pinfunction "P7_3_11") (pintype "bidirectional"))
    )
    (net (code "12") (name "ETH_RX_ER") (class "Default")
      (node (ref "R32") (pin "P$1") (pinfunction "1_P$1") (pintype "passive"))
      (node (ref "U4") (pin "12") (pinfunction "P7_4_12") (pintype "bidirectional"))
    )
    (net (code "13") (name "ETH_TXD0") (class "Default")
      (node (ref "U3") (pin "20") (pinfunction "TXD0_20") (pintype "input"))
      (node (ref "U4") (pin "8") (pinfunction "P7_0_8") (pintype "bidirectional"))
    )
    (net (code "14") (name "ETH_TXD1") (class "Default")
      (node (ref "U3") (pin "21") (pinfunction "TXD1_21") (pintype "bidirectional"))
      (node (ref "U4") (pin "7") (pinfunction "P4_6_7") (pintype "bidirectional"))
    )
    (net (code "15") (name "ETH_TXD_EN") (class "Default")
      (node (ref "U3") (pin "19") (pinfunction "TXEN_19") (pintype "input"))
      (node (ref "U4") (pin "6") (pinfunction "P4_5_6") (pintype "bidirectional"))
    )
    (net (code "16") (name "F0_OUT") (class "Default")
      (node (ref "J13") (pin "P$1") (pinfunction "P$1_P$1") (pintype "bidirectional"))
      (node (ref "J14") (pin "P$1") (pinfunction "P$1_P$1") (pintype "bidirectional"))
      (node (ref "J5") (pin "P$1") (pinfunction "P$1_P$1") (pintype "bidirectional"))
      (node (ref "J6") (pin "P$1") (pinfunction "P$1_P$1") (pintype "bidirectional"))
      (node (ref "U13") (pin "3") (pinfunction "C(3)_3") (pintype "input"))
      (node (ref "U17") (pin "3") (pinfunction "C(3)_3") (pintype "input"))
      (node (ref "U33") (pin "3") (pinfunction "C(3)_3") (pintype "input"))
      (node (ref "U8") (pin "3") (pinfunction "C(3)_3") (pintype "input"))
    )
    (net (code "17") (name "F1_OUT") (class "Default")
      (node (ref "J13") (pin "P$2") (pinfunction "P$2_P$2") (pintype "bidirectional"))
      (node (ref "J14") (pin "P$2") (pinfunction "P$2_P$2") (pintype "bidirectional"))
      (node (ref "J5") (pin "P$2") (pinfunction "P$2_P$2") (pintype "bidirectional"))
      (node (ref "J6") (pin "P$2") (pinfunction "P$2_P$2") (pintype "bidirectional"))
      (node (ref "U14") (pin "3") (pinfunction "C(3)_3") (pintype "input"))
      (node (ref "U18") (pin "3") (pinfunction "C(3)_3") (pintype "input"))
      (node (ref "U34") (pin "3") (pinfunction "C(3)_3") (pintype "input"))
      (node (ref "U9") (pin "3") (pinfunction "C(3)_3") (pintype "input"))
    )
    (net (code "18") (name "F2_OUT") (class "Default")
      (node (ref "J13") (pin "P$3") (pinfunction "P$3_P$3") (pintype "bidirectional"))
      (node (ref "J14") (pin "P$3") (pinfunction "P$3_P$3") (pintype "bidirectional"))
      (node (ref "J5") (pin "P$3") (pinfunction "P$3_P$3") (pintype "bidirectional"))
      (node (ref "J6") (pin "P$3") (pinfunction "P$3_P$3") (pintype "bidirectional"))
      (node (ref "U12") (pin "3") (pinfunction "C(3)_3") (pintype "input"))
      (node (ref "U16") (pin "3") (pinfunction "C(3)_3") (pintype "input"))
      (node (ref "U32") (pin "3") (pinfunction "C(3)_3") (pintype "input"))
      (node (ref "U7") (pin "3") (pinfunction "C(3)_3") (pintype "input"))
    )
    (net (code "19") (name "F3_OUT") (class "Default")
      (node (ref "J13") (pin "P$4") (pinfunction "P$4_P$4") (pintype "bidirectional"))
      (node (ref "J14") (pin "P$4") (pinfunction "P$4_P$4") (pintype "bidirectional"))
      (node (ref "J5") (pin "P$4") (pinfunction "P$4_P$4") (pintype "bidirectional"))
      (node (ref "J6") (pin "P$4") (pinfunction "P$4_P$4") (pintype "bidirectional"))
      (node (ref "U10") (pin "3") (pinfunction "C(3)_3") (pintype "input"))
      (node (ref "U15") (pin "3") (pinfunction "C(3)_3") (pintype "input"))
      (node (ref "U19") (pin "3") (pinfunction "C(3)_3") (pintype "input"))
      (node (ref "U35") (pin "3") (pinfunction "C(3)_3") (pintype "input"))
    )
    (net (code "20") (name "GND") (class "Default")
      (node (ref "C10") (pin "P$1") (pinfunction "1_P$1") (pintype "passive"))
      (node (ref "C11") (pin "P$2") (pinfunction "2_P$2") (pintype "passive"))
      (node (ref "C13") (pin "P$1") (pinfunction "1_P$1") (pintype "passive"))
      (node (ref "C14") (pin "P$1") (pinfunction "1_P$1") (pintype "passive"))
      (node (ref "C15") (pin "2") (pinfunction "2_2") (pintype "passive"))
      (node (ref "C16") (pin "P$2") (pinfunction "2_P$2") (pintype "passive"))
      (node (ref "C30") (pin "P$1") (pinfunction "1_P$1") (pintype "passive"))
      (node (ref "C31") (pin "P$2") (pinfunction "2_P$2") (pintype "passive"))
      (node (ref "C32") (pin "P$2") (pinfunction "2_P$2") (pintype "passive"))
      (node (ref "C33") (pin "P$2") (pinfunction "2_P$2") (pintype "passive"))
      (node (ref "C34") (pin "P$2") (pinfunction "2_P$2") (pintype "passive"))
      (node (ref "C35") (pin "P$2") (pinfunction "2_P$2") (pintype "passive"))
      (node (ref "C36") (pin "P$1") (pinfunction "1_P$1") (pintype "passive"))
      (node (ref "C37") (pin "P$1") (pinfunction "1_P$1") (pintype "passive"))
      (node (ref "C38") (pin "P$2") (pinfunction "2_P$2") (pintype "passive"))
      (node (ref "C39") (pin "P$2") (pinfunction "2_P$2") (pintype "passive"))
      (node (ref "C40") (pin "P$2") (pinfunction "2_P$2") (pintype "passive"))
      (node (ref "C41") (pin "P$2") (pinfunction "2_P$2") (pintype "passive"))
      (node (ref "C42") (pin "P$2") (pinfunction "2_P$2") (pintype "passive"))
      (node (ref "C43") (pin "2") (pinfunction "2_2") (pintype "passive"))
      (node (ref "C44") (pin "P$2") (pinfunction "2_P$2") (pintype "passive"))
      (node (ref "C45") (pin "P$2") (pinfunction "2_P$2") (pintype "passive"))
      (node (ref "C46") (pin "P$2") (pinfunction "2_P$2") (pintype "passive"))
      (node (ref "C47") (pin "P$2") (pinfunction "2_P$2") (pintype "passive"))
      (node (ref "C48") (pin "2") (pinfunction "2_2") (pintype "passive"))
      (node (ref "C49") (pin "P$2") (pinfunction "2_P$2") (pintype "passive"))
      (node (ref "C5") (pin "P$2") (pinfunction "2_P$2") (pintype "passive"))
      (node (ref "C50") (pin "P$2") (pinfunction "2_P$2") (pintype "passive"))
      (node (ref "C51") (pin "P$2") (pinfunction "2_P$2") (pintype "passive"))
      (node (ref "C52") (pin "P$2") (pinfunction "2_P$2") (pintype "passive"))
      (node (ref "C53") (pin "P$2") (pinfunction "2_P$2") (pintype "passive"))
      (node (ref "C54") (pin "P$1") (pinfunction "1_P$1") (pintype "passive"))
      (node (ref "C55") (pin "P$1") (pinfunction "1_P$1") (pintype "passive"))
      (node (ref "C56") (pin "P$1") (pinfunction "1_P$1") (pintype "passive"))
      (node (ref "C57") (pin "P$2") (pinfunction "2_P$2") (pintype "passive"))
      (node (ref "C58") (pin "P$2") (pinfunction "2_P$2") (pintype "passive"))
      (node (ref "C59") (pin "P$2") (pinfunction "2_P$2") (pintype "passive"))
      (node (ref "C60") (pin "P$2") (pinfunction "2_P$2") (pintype "passive"))
      (node (ref "C61") (pin "P$1") (pinfunction "1_P$1") (pintype "passive"))
      (node (ref "C8") (pin "P$2") (pinfunction "2_P$2") (pintype "passive"))
      (node (ref "J1") (pin "1") (pinfunction "1_1") (pintype "passive"))
      (node (ref "J1") (pin "2") (pinfunction "2_2") (pintype "passive"))
      (node (ref "J11") (pin "10") (pinfunction "10_10") (pintype "passive"))
      (node (ref "J11") (pin "6") (pinfunction "6_6") (pintype "passive"))
      (node (ref "J11") (pin "8") (pinfunction "8_8") (pintype "passive"))
      (node (ref "J16") (pin "10") (pinfunction "10_10") (pintype "passive"))
      (node (ref "J16") (pin "2") (pinfunction "2_2") (pintype "passive"))
      (node (ref "J16") (pin "4") (pinfunction "4_4") (pintype "passive"))
      (node (ref "J16") (pin "6") (pinfunction "6_6") (pintype "passive"))
      (node (ref "J16") (pin "8") (pinfunction "8_8") (pintype "passive"))
      (node (ref "J2") (pin "P$5") (pinfunction "GND_P$5") (pintype "bidirectional"))
      (node (ref "J3") (pin "GND") (pinfunction "GND_GND") (pintype "power_in"))
      (node (ref "J4") (pin "10") (pinfunction "GLO_10") (pintype "bidirectional"))
      (node (ref "J4") (pin "8") (pinfunction "P8_8") (pintype "bidirectional"))
      (node (ref "J9") (pin "6") (pinfunction "SUPPLY_VOLTAGE_GROUND_6") (pintype "power_in"))
      (node (ref "LED3") (pin "C") (pinfunction "C_C") (pintype "passive"))
      (node (ref "R16") (pin "P$1") (pinfunction "1_P$1") (pintype "passive"))
      (node (ref "R17") (pin "P$1") (pinfunction "1_P$1") (pintype "passive"))
      (node (ref "R19") (pin "P$1") (pinfunction "1_P$1") (pintype "passive"))
      (node (ref "R25") (pin "P$1") (pinfunction "1_P$1") (pintype "passive"))
      (node (ref "R7") (pin "P$1") (pinfunction "1_P$1") (pintype "passive"))
      (node (ref "U$1") (pin "P$2") (pinfunction "2_P$2") (pintype "passive"))
      (node (ref "U$10") (pin "P$2") (pinfunction "2_P$2") (pintype "passive"))
      (node (ref "U$12") (pin "P$2") (pinfunction "2_P$2") (pintype "passive"))
      (node (ref "U$13") (pin "P$2") (pinfunction "2_P$2") (pintype "passive"))
      (node (ref "U$14") (pin "P$2") (pinfunction "2_P$2") (pintype "passive"))
      (node (ref "U$15") (pin "P$2") (pinfunction "2_P$2") (pintype "passive"))
      (node (ref "U$16") (pin "P$2") (pinfunction "2_P$2") (pintype "passive"))
      (node (ref "U$17") (pin "P$2") (pinfunction "2_P$2") (pintype "passive"))
      (node (ref "U$18") (pin "P$2") (pinfunction "2_P$2") (pintype "passive"))
      (node (ref "U$3") (pin "2") (pinfunction "2_2") (pintype "bidirectional"))
      (node (ref "U$3") (pin "4") (pinfunction "4_4") (pintype "bidirectional"))
      (node (ref "U$32") (pin "P$2") (pinfunction "2_P$2") (pintype "passive"))
      (node (ref "U$33") (pin "P$2") (pinfunction "2_P$2") (pintype "passive"))
      (node (ref "U$34") (pin "P$2") (pinfunction "2_P$2") (pintype "passive"))
      (node (ref "U$35") (pin "P$2") (pinfunction "2_P$2") (pintype "passive"))
      (node (ref "U$4") (pin "P$2") (pinfunction "2_P$2") (pintype "passive"))
      (node (ref "U$5") (pin "P$2") (pinfunction "2_P$2") (pintype "passive"))
      (node (ref "U$6") (pin "P$2") (pinfunction "2_P$2") (pintype "passive"))
      (node (ref "U$8") (pin "P$2") (pinfunction "2_P$2") (pintype "passive"))
      (node (ref "U10") (pin "2") (pinfunction "E(1)_2") (pintype "output"))
      (node (ref "U12") (pin "2") (pinfunction "E(1)_2") (pintype "output"))
      (node (ref "U13") (pin "2") (pinfunction "E(1)_2") (pintype "output"))
      (node (ref "U14") (pin "2") (pinfunction "E(1)_2") (pintype "output"))
      (node (ref "U15") (pin "2") (pinfunction "E(1)_2") (pintype "output"))
      (node (ref "U16") (pin "2") (pinfunction "E(1)_2") (pintype "output"))
      (node (ref "U17") (pin "2") (pinfunction "E(1)_2") (pintype "output"))
      (node (ref "U18") (pin "2") (pinfunction "E(1)_2") (pintype "output"))
      (node (ref "U19") (pin "2") (pinfunction "E(1)_2") (pintype "output"))
      (node (ref "U2") (pin "2") (pinfunction "GND_2") (pintype "input"))
      (node (ref "U3") (pin "22") (pinfunction "GND_22") (pintype "power_in"))
      (node (ref "U3") (pin "25") (pinfunction "25_25") (pintype "passive"))
      (node (ref "U32") (pin "2") (pinfunction "E(1)_2") (pintype "output"))
      (node (ref "U33") (pin "2") (pinfunction "E(1)_2") (pintype "output"))
      (node (ref "U34") (pin "2") (pinfunction "E(1)_2") (pintype "output"))
      (node (ref "U35") (pin "2") (pinfunction "E(1)_2") (pintype "output"))
      (node (ref "U4") (pin "111") (pinfunction "VSS(IO)5_111") (pintype "bidirectional"))
      (node (ref "U4") (pin "124") (pinfunction "VSS(IO)6_124") (pintype "bidirectional"))
      (node (ref "U4") (pin "139") (pinfunction "VSS(IO)7_139") (pintype "bidirectional"))
      (node (ref "U4") (pin "150") (pinfunction "VSS(IO)8_150") (pintype "bidirectional"))
      (node (ref "U4") (pin "156") (pinfunction "AVSS0_156") (pintype "bidirectional"))
      (node (ref "U4") (pin "170") (pinfunction "VSS(IO)9_170") (pintype "bidirectional"))
      (node (ref "U4") (pin "22") (pinfunction "VSS1_22") (pintype "bidirectional"))
      (node (ref "U4") (pin "28") (pinfunction "AVSS_USBHS_28") (pintype "bidirectional"))
      (node (ref "U4") (pin "29") (pinfunction "PVSS_USBHS_29") (pintype "bidirectional"))
      (node (ref "U4") (pin "30") (pinfunction "VSS2_USBHS_30") (pintype "bidirectional"))
      (node (ref "U4") (pin "33") (pinfunction "VSS1_USBHS_33") (pintype "bidirectional"))
      (node (ref "U4") (pin "35") (pinfunction "VSSIO_35") (pintype "bidirectional"))
      (node (ref "U4") (pin "45") (pinfunction "VSS_USB_45") (pintype "bidirectional"))
      (node (ref "U4") (pin "60") (pinfunction "VSS(IO)2_60") (pintype "bidirectional"))
      (node (ref "U4") (pin "63") (pinfunction "VSS(IO/DCDC)_63") (pintype "bidirectional"))
      (node (ref "U4") (pin "66") (pinfunction "VCC_DCDC(IO/DCDC)_66") (pintype "bidirectional"))
      (node (ref "U4") (pin "83") (pinfunction "VSS(IO)3_83") (pintype "bidirectional"))
      (node (ref "U4") (pin "98") (pinfunction "VSS(IO)4_98") (pintype "bidirectional"))
      (node (ref "U7") (pin "2") (pinfunction "E(1)_2") (pintype "output"))
      (node (ref "U8") (pin "2") (pinfunction "E(1)_2") (pintype "output"))
      (node (ref "U9") (pin "2") (pinfunction "E(1)_2") (pintype "output"))
      (node (ref "X4") (pin "2") (pinfunction "2_2") (pintype "bidirectional"))
      (node (ref "X4") (pin "4") (pinfunction "4_4") (pintype "bidirectional"))
    )
    (net (code "21") (name "GNDE") (class "Default")
      (node (ref "J1") (pin "10") (pinfunction "10_10") (pintype "passive"))
      (node (ref "J1") (pin "9") (pinfunction "9_9") (pintype "passive"))
      (node (ref "J2") (pin "P$6") (pinfunction "SHIELD1_P$6") (pintype "bidirectional"))
      (node (ref "J2") (pin "P$7") (pinfunction "SHIELD2_P$7") (pintype "bidirectional"))
      (node (ref "J2") (pin "P$8") (pinfunction "SHIELD3_P$8") (pintype "bidirectional"))
      (node (ref "J2") (pin "P$9") (pinfunction "SHIELD4_P$9") (pintype "bidirectional"))
      (node (ref "J3") (pin "SHLD1") (pinfunction "SHIELD_1_SHLD1") (pintype "bidirectional"))
      (node (ref "J3") (pin "SHLD2") (pinfunction "SHIELD_2_SHLD2") (pintype "bidirectional"))
      (node (ref "J4") (pin "13") (pinfunction "GNDE0_13") (pintype "bidirectional"))
      (node (ref "J4") (pin "14") (pinfunction "GNDE1_14") (pintype "bidirectional"))
      (node (ref "J9") (pin "S1") (pinfunction "SHIELD_S1") (pintype "passive"))
      (node (ref "J9") (pin "S2") (pinfunction "SHIELD_S2") (pintype "passive"))
      (node (ref "J9") (pin "S3") (pinfunction "SHIELD_S3") (pintype "passive"))
      (node (ref "J9") (pin "S4") (pinfunction "SHIELD_S4") (pintype "passive"))
    )
    (net (code "22") (name "GP4") (class "Default")
      (node (ref "U4") (pin "49") (pinfunction "P2_7_49") (pintype "bidirectional"))
    )
    (net (code "23") (name "ID") (class "Default")
      (node (ref "J2") (pin "P$4") (pinfunction "ID_P$4") (pintype "bidirectional"))
    )
    (net (code "24") (name "IIC_0_SCL") (class "Default")
      (node (ref "J7") (pin "10") (pinfunction "10_10") (pintype "passive"))
      (node (ref "R11") (pin "P$2") (pinfunction "2_P$2") (pintype "passive"))
      (node (ref "U4") (pin "1") (pinfunction "P4_0_1") (pintype "bidirectional"))
    )
    (net (code "25") (name "IIC_0_SDA") (class "Default")
      (node (ref "J7") (pin "9") (pinfunction "9_9") (pintype "passive"))
      (node (ref "R14") (pin "P$2") (pinfunction "2_P$2") (pintype "passive"))
      (node (ref "U4") (pin "2") (pinfunction "P4_1_2") (pintype "bidirectional"))
    )
    (net (code "26") (name "IIC_1_SCL") (class "Default")
      (node (ref "J10") (pin "P$5") (pinfunction "P$5_P$5") (pintype "bidirectional"))
      (node (ref "R20") (pin "P$2") (pinfunction "2_P$2") (pintype "passive"))
      (node (ref "U4") (pin "132") (pinfunction "P1_0_132") (pintype "bidirectional"))
    )
    (net (code "27") (name "IIC_1_SDA") (class "Default")
      (node (ref "J10") (pin "P$6") (pinfunction "P$6_P$6") (pintype "bidirectional"))
      (node (ref "R21") (pin "P$2") (pinfunction "2_P$2") (pintype "passive"))
      (node (ref "U4") (pin "131") (pinfunction "P1_1_131") (pintype "bidirectional"))
    )
    (net (code "28") (name "INT_AI_LS_0") (class "Default")
      (node (ref "J15") (pin "P$1") (pinfunction "P$1_P$1") (pintype "bidirectional"))
      (node (ref "U4") (pin "3") (pinfunction "P4_2_3") (pintype "bidirectional"))
    )
    (net (code "29") (name "INT_AI_LS_1") (class "Default")
      (node (ref "J15") (pin "P$2") (pinfunction "P$2_P$2") (pintype "bidirectional"))
      (node (ref "U4") (pin "43") (pinfunction "P4_8_43") (pintype "bidirectional"))
    )
    (net (code "30") (name "INT_AI_LS_2") (class "Default")
      (node (ref "J15") (pin "P$3") (pinfunction "P$3_P$3") (pintype "bidirectional"))
      (node (ref "U4") (pin "53") (pinfunction "P2_3_53") (pintype "bidirectional"))
    )
    (net (code "31") (name "INT_AI_LS_3") (class "Default")
      (node (ref "J15") (pin "P$4") (pinfunction "P$4_P$4") (pintype "bidirectional"))
      (node (ref "U4") (pin "54") (pinfunction "P2_2_54") (pintype "bidirectional"))
    )
    (net (code "32") (name "INT_MI_01") (class "Default")
      (node (ref "J10") (pin "P$39") (pinfunction "P$39_P$39") (pintype "bidirectional"))
      (node (ref "U4") (pin "87") (pinfunction "P3_1_87") (pintype "bidirectional"))
    )
    (net (code "33") (name "INT_MI_02") (class "Default")
      (node (ref "J10") (pin "P$40") (pinfunction "P$40_P$40") (pintype "bidirectional"))
      (node (ref "U4") (pin "86") (pinfunction "P3_2_86") (pintype "bidirectional"))
    )
    (net (code "34") (name "INT_MI_03") (class "Default")
      (node (ref "J10") (pin "P$9") (pinfunction "P$9_P$9") (pintype "bidirectional"))
      (node (ref "U4") (pin "128") (pinfunction "P1_4_128") (pintype "bidirectional"))
    )
    (net (code "35") (name "INT_MI_04") (class "Default")
      (node (ref "J10") (pin "P$10") (pinfunction "P$10_P$10") (pintype "bidirectional"))
      (node (ref "U4") (pin "127") (pinfunction "P1_5_127") (pintype "bidirectional"))
    )
    (net (code "36") (name "INT_MI_05") (class "Default")
      (node (ref "J10") (pin "P$1") (pinfunction "P$1_P$1") (pintype "bidirectional"))
    )
    (net (code "37") (name "LED1{slash}SPEED") (class "Default")
      (node (ref "J4") (pin "11") (pinfunction "YLO_11") (pintype "bidirectional"))
      (node (ref "U3") (pin "23") (pinfunction "LED0/ANEN_SPEED_23") (pintype "bidirectional"))
    )
    (net (code "38") (name "M0_DIR") (class "Default")
      (node (ref "RXS4") (pin "P$1") (pinfunction "1_P$1") (pintype "passive"))
      (node (ref "U4") (pin "39") (pinfunction "P4_12_39") (pintype "bidirectional"))
    )
    (net (code "39") (name "M0_STEP") (class "Default")
      (node (ref "RXS2") (pin "P$1") (pinfunction "1_P$1") (pintype "passive"))
      (node (ref "U4") (pin "16") (pinfunction "PB_0_16") (pintype "bidirectional"))
    )
    (net (code "40") (name "M1_DIR") (class "Default")
      (node (ref "RYS7") (pin "P$1") (pinfunction "1_P$1") (pintype "passive"))
      (node (ref "U4") (pin "40") (pinfunction "P4_11_40") (pintype "bidirectional"))
    )
    (net (code "41") (name "M1_STEP") (class "Default")
      (node (ref "RYS3") (pin "P$1") (pinfunction "1_P$1") (pintype "passive"))
      (node (ref "U4") (pin "36") (pinfunction "P4_15_36") (pintype "bidirectional"))
    )
    (net (code "42") (name "M2_DIR") (class "Default")
      (node (ref "RZS4") (pin "P$1") (pinfunction "1_P$1") (pintype "passive"))
      (node (ref "U4") (pin "41") (pinfunction "P4_10_41") (pintype "bidirectional"))
    )
    (net (code "43") (name "M2_STEP") (class "Default")
      (node (ref "RZS2") (pin "P$1") (pinfunction "1_P$1") (pintype "passive"))
      (node (ref "U4") (pin "37") (pinfunction "P4_14_37") (pintype "bidirectional"))
    )
    (net (code "44") (name "M3_DIR") (class "Default")
      (node (ref "RYS8") (pin "P$1") (pinfunction "1_P$1") (pintype "passive"))
      (node (ref "U4") (pin "42") (pinfunction "P4_9_42") (pintype "bidirectional"))
    )
    (net (code "45") (name "M3_STEP") (class "Default")
      (node (ref "RYS4") (pin "P$1") (pinfunction "1_P$1") (pintype "passive"))
      (node (ref "U4") (pin "38") (pinfunction "P4_13_38") (pintype "bidirectional"))
    )
    (net (code "46") (name "NC") (class "Default")
      (node (ref "J4") (pin "7") (pinfunction "P7_7") (pintype "bidirectional"))
    )
    (net (code "47") (name "Net-(C16-1)") (class "Default")
      (node (ref "C16") (pin "P$1") (pinfunction "1_P$1") (pintype "passive"))
      (node (ref "J2") (pin "P$1") (pinfunction "VBUS_P$1") (pintype "bidirectional"))
      (node (ref "R4") (pin "P$2") (pinfunction "2_P$2") (pintype "passive"))
      (node (ref "R7") (pin "P$2") (pinfunction "2_P$2") (pintype "passive"))
    )
    (net (code "48") (name "Net-(C31-1)") (class "Default")
      (node (ref "C31") (pin "P$1") (pinfunction "1_P$1") (pintype "passive"))
      (node (ref "U4") (pin "62") (pinfunction "VCL1_62") (pintype "bidirectional"))
    )
    (net (code "49") (name "Net-(C37-2)") (class "Default")
      (node (ref "C37") (pin "P$2") (pinfunction "2_P$2") (pintype "passive"))
      (node (ref "U4") (pin "148") (pinfunction "VCL2_148") (pintype "bidirectional"))
    )
    (net (code "50") (name "Net-(C38-1)") (class "Default")
      (node (ref "C38") (pin "P$1") (pinfunction "1_P$1") (pintype "passive"))
      (node (ref "U4") (pin "19") (pinfunction "VCLO_19") (pintype "bidirectional"))
    )
    (net (code "51") (name "Net-(C44-1)") (class "Default")
      (node (ref "C43") (pin "1") (pinfunction "1_1") (pintype "passive"))
      (node (ref "C44") (pin "P$1") (pinfunction "1_P$1") (pintype "passive"))
      (node (ref "FB2/2") (pin "2") (pinfunction "P$2_2") (pintype "bidirectional"))
      (node (ref "U3") (pin "2") (pinfunction "VDDA_3.3_2") (pintype "power_in"))
    )
    (net (code "52") (name "Net-(J2-D+)") (class "Default")
      (node (ref "J2") (pin "P$3") (pinfunction "D+_P$3") (pintype "bidirectional"))
      (node (ref "R6") (pin "P$2") (pinfunction "2_P$2") (pintype "passive"))
    )
    (net (code "53") (name "Net-(J2-D-)") (class "Default")
      (node (ref "J2") (pin "P$2") (pinfunction "D-_P$2") (pintype "bidirectional"))
      (node (ref "R5") (pin "P$2") (pinfunction "2_P$2") (pintype "passive"))
    )
    (net (code "54") (name "Net-(R13-1)") (class "Default")
      (node (ref "LED3") (pin "A") (pinfunction "A_A") (pintype "passive"))
      (node (ref "R13") (pin "P$1") (pinfunction "1_P$1") (pintype "passive"))
    )
    (net (code "55") (name "Net-(R16-2)") (class "Default")
      (node (ref "R16") (pin "P$2") (pinfunction "2_P$2") (pintype "passive"))
      (node (ref "U4") (pin "65") (pinfunction "VLO2(DCDC)_65") (pintype "bidirectional"))
    )
    (net (code "56") (name "Net-(R17-2)") (class "Default")
      (node (ref "R17") (pin "P$2") (pinfunction "2_P$2") (pintype "passive"))
      (node (ref "U4") (pin "64") (pinfunction "VLO1(DCDC)_64") (pintype "bidirectional"))
    )
    (net (code "57") (name "Net-(R19-2)") (class "Default")
      (node (ref "R19") (pin "P$2") (pinfunction "2_P$2") (pintype "passive"))
      (node (ref "U4") (pin "27") (pinfunction "USBHS_RREF_27") (pintype "bidirectional"))
    )
    (net (code "58") (name "Net-(RXS2-2)") (class "Default")
      (node (ref "RXS2") (pin "P$2") (pinfunction "2_P$2") (pintype "passive"))
      (node (ref "U$5") (pin "P$1") (pinfunction "1_P$1") (pintype "passive"))
      (node (ref "U8") (pin "1") (pinfunction "B(2)_1") (pintype "input"))
    )
    (net (code "59") (name "Net-(RXS3-2)") (class "Default")
      (node (ref "RXS3") (pin "P$2") (pinfunction "2_P$2") (pintype "passive"))
      (node (ref "U$12") (pin "P$1") (pinfunction "1_P$1") (pintype "passive"))
      (node (ref "U13") (pin "1") (pinfunction "B(2)_1") (pintype "input"))
    )
    (net (code "60") (name "Net-(RXS4-2)") (class "Default")
      (node (ref "RXS4") (pin "P$2") (pinfunction "2_P$2") (pintype "passive"))
      (node (ref "U$16") (pin "P$1") (pinfunction "1_P$1") (pintype "passive"))
      (node (ref "U17") (pin "1") (pinfunction "B(2)_1") (pintype "input"))
    )
    (net (code "61") (name "Net-(RXS8-2)") (class "Default")
      (node (ref "RXS8") (pin "P$2") (pinfunction "2_P$2") (pintype "passive"))
      (node (ref "U$33") (pin "P$1") (pinfunction "1_P$1") (pintype "passive"))
      (node (ref "U33") (pin "1") (pinfunction "B(2)_1") (pintype "input"))
    )
    (net (code "62") (name "Net-(RYS3-2)") (class "Default")
      (node (ref "RYS3") (pin "P$2") (pinfunction "2_P$2") (pintype "passive"))
      (node (ref "U$6") (pin "P$1") (pinfunction "1_P$1") (pintype "passive"))
      (node (ref "U9") (pin "1") (pinfunction "B(2)_1") (pintype "input"))
    )
    (net (code "63") (name "Net-(RYS4-2)") (class "Default")
      (node (ref "RYS4") (pin "P$2") (pinfunction "2_P$2") (pintype "passive"))
      (node (ref "U$8") (pin "P$1") (pinfunction "1_P$1") (pintype "passive"))
      (node (ref "U10") (pin "1") (pinfunction "B(2)_1") (pintype "input"))
    )
    (net (code "64") (name "Net-(RYS5-2)") (class "Default")
      (node (ref "RYS5") (pin "P$2") (pinfunction "2_P$2") (pintype "passive"))
      (node (ref "U$13") (pin "P$1") (pinfunction "1_P$1") (pintype "passive"))
      (node (ref "U14") (pin "1") (pinfunction "B(2)_1") (pintype "input"))
    )
    (net (code "65") (name "Net-(RYS6-2)") (class "Default")
      (node (ref "RYS6") (pin "P$2") (pinfunction "2_P$2") (pintype "passive"))
      (node (ref "U$14") (pin "P$1") (pinfunction "1_P$1") (pintype "passive"))
      (node (ref "U15") (pin "1") (pinfunction "B(2)_1") (pintype "input"))
    )
    (net (code "66") (name "Net-(RYS7-2)") (class "Default")
      (node (ref "RYS7") (pin "P$2") (pinfunction "2_P$2") (pintype "passive"))
      (node (ref "U$17") (pin "P$1") (pinfunction "1_P$1") (pintype "passive"))
      (node (ref "U18") (pin "1") (pinfunction "B(2)_1") (pintype "input"))
    )
    (net (code "67") (name "Net-(RYS8-2)") (class "Default")
      (node (ref "RYS8") (pin "P$2") (pinfunction "2_P$2") (pintype "passive"))
      (node (ref "U$18") (pin "P$1") (pinfunction "1_P$1") (pintype "passive"))
      (node (ref "U19") (pin "1") (pinfunction "B(2)_1") (pintype "input"))
    )
    (net (code "68") (name "Net-(RYS15-2)") (class "Default")
      (node (ref "RYS15") (pin "P$2") (pinfunction "2_P$2") (pintype "passive"))
      (node (ref "U$34") (pin "P$1") (pinfunction "1_P$1") (pintype "passive"))
      (node (ref "U34") (pin "1") (pinfunction "B(2)_1") (pintype "input"))
    )
    (net (code "69") (name "Net-(RYS16-2)") (class "Default")
      (node (ref "RYS16") (pin "P$2") (pinfunction "2_P$2") (pintype "passive"))
      (node (ref "U$35") (pin "P$1") (pinfunction "1_P$1") (pintype "passive"))
      (node (ref "U35") (pin "1") (pinfunction "B(2)_1") (pintype "input"))
    )
    (net (code "70") (name "Net-(RZS2-2)") (class "Default")
      (node (ref "RZS2") (pin "P$2") (pinfunction "2_P$2") (pintype "passive"))
      (node (ref "U$1") (pin "P$1") (pinfunction "1_P$1") (pintype "passive"))
      (node (ref "U7") (pin "1") (pinfunction "B(2)_1") (pintype "input"))
    )
    (net (code "71") (name "Net-(RZS3-2)") (class "Default")
      (node (ref "RZS3") (pin "P$2") (pinfunction "2_P$2") (pintype "passive"))
      (node (ref "U$10") (pin "P$1") (pinfunction "1_P$1") (pintype "passive"))
      (node (ref "U12") (pin "1") (pinfunction "B(2)_1") (pintype "input"))
    )
    (net (code "72") (name "Net-(RZS4-2)") (class "Default")
      (node (ref "RZS4") (pin "P$2") (pinfunction "2_P$2") (pintype "passive"))
      (node (ref "U$15") (pin "P$1") (pinfunction "1_P$1") (pintype "passive"))
      (node (ref "U16") (pin "1") (pinfunction "B(2)_1") (pintype "input"))
    )
    (net (code "73") (name "Net-(RZS8-2)") (class "Default")
      (node (ref "RZS8") (pin "P$2") (pinfunction "2_P$2") (pintype "passive"))
      (node (ref "U$32") (pin "P$1") (pinfunction "1_P$1") (pintype "passive"))
      (node (ref "U32") (pin "1") (pinfunction "B(2)_1") (pintype "input"))
    )
    (net (code "74") (name "P0_00") (class "Default")
      (node (ref "J7") (pin "3") (pinfunction "3_3") (pintype "passive"))
      (node (ref "U4") (pin "169") (pinfunction "P0_0/AN0\\00_169") (pintype "bidirectional"))
    )
    (net (code "75") (name "P0_01") (class "Default")
      (node (ref "J7") (pin "4") (pinfunction "4_4") (pintype "passive"))
      (node (ref "U4") (pin "168") (pinfunction "P0_1/AN001_168") (pintype "bidirectional"))
    )
    (net (code "76") (name "P0_02") (class "Default")
      (node (ref "J7") (pin "1") (pinfunction "1_1") (pintype "passive"))
      (node (ref "U4") (pin "167") (pinfunction "P0_2/AN002_167") (pintype "bidirectional"))
    )
    (net (code "77") (name "P0_03") (class "Default")
      (node (ref "J7") (pin "2") (pinfunction "2_2") (pintype "passive"))
      (node (ref "U4") (pin "166") (pinfunction "P0_3/PGAVSS000_166") (pintype "bidirectional"))
    )
    (net (code "78") (name "P0_04") (class "Default")
      (node (ref "J8") (pin "9") (pinfunction "9_9") (pintype "passive"))
      (node (ref "U4") (pin "165") (pinfunction "P0_4/AN100_165") (pintype "bidirectional"))
    )
    (net (code "79") (name "P0_05") (class "Default")
      (node (ref "J8") (pin "10") (pinfunction "10_10") (pintype "passive"))
      (node (ref "U4") (pin "164") (pinfunction "P0_5/AN101_164") (pintype "bidirectional"))
    )
    (net (code "80") (name "P0_06") (class "Default")
      (node (ref "J8") (pin "7") (pinfunction "7_7") (pintype "passive"))
      (node (ref "U4") (pin "163") (pinfunction "P0_6/AN102_163") (pintype "bidirectional"))
    )
    (net (code "81") (name "P0_07") (class "Default")
      (node (ref "J8") (pin "8") (pinfunction "8_8") (pintype "passive"))
      (node (ref "U4") (pin "162") (pinfunction "P0_7/PGVSS100_162") (pintype "bidirectional"))
    )
    (net (code "82") (name "P0_08") (class "Default")
      (node (ref "J8") (pin "5") (pinfunction "5_5") (pintype "passive"))
      (node (ref "U4") (pin "161") (pinfunction "P0_8/AN003_161") (pintype "bidirectional"))
    )
    (net (code "83") (name "P0_09") (class "Default")
      (node (ref "J8") (pin "6") (pinfunction "6_6") (pintype "passive"))
      (node (ref "U4") (pin "160") (pinfunction "P0_9/AN004_160") (pintype "bidirectional"))
    )
    (net (code "84") (name "P0_14") (class "Default")
      (node (ref "J8") (pin "3") (pinfunction "3_3") (pintype "passive"))
      (node (ref "U4") (pin "152") (pinfunction "P0_14/DA0/AN005/AN105_152") (pintype "bidirectional"))
    )
    (net (code "85") (name "P0_15") (class "Default")
      (node (ref "J8") (pin "4") (pinfunction "4_4") (pintype "passive"))
      (node (ref "U4") (pin "151") (pinfunction "P0_15/DA1/AN006/AN106_151") (pintype "bidirectional"))
    )
    (net (code "86") (name "P1_02") (class "Default")
      (node (ref "J10") (pin "P$7") (pinfunction "P$7_P$7") (pintype "bidirectional"))
      (node (ref "U4") (pin "130") (pinfunction "P1_2_130") (pintype "bidirectional"))
    )
    (net (code "87") (name "P1_03") (class "Default")
      (node (ref "J10") (pin "P$8") (pinfunction "P$8_P$8") (pintype "bidirectional"))
      (node (ref "U4") (pin "129") (pinfunction "P1_3_129") (pintype "bidirectional"))
    )
    (net (code "88") (name "P1_06") (class "Default")
      (node (ref "J10") (pin "P$11") (pinfunction "P$11_P$11") (pintype "bidirectional"))
      (node (ref "U4") (pin "126") (pinfunction "P1_6_126") (pintype "bidirectional"))
    )
    (net (code "89") (name "P1_07") (class "Default")
      (node (ref "J10") (pin "P$12") (pinfunction "P$12_P$12") (pintype "bidirectional"))
      (node (ref "U4") (pin "125") (pinfunction "P1_7_125") (pintype "bidirectional"))
    )
    (net (code "90") (name "P1_11") (class "Default")
      (node (ref "J10") (pin "P$38") (pinfunction "P$38_P$38") (pintype "bidirectional"))
      (node (ref "U4") (pin "92") (pinfunction "P1_11_92") (pintype "bidirectional"))
    )
    (net (code "91") (name "P1_12") (class "Default")
      (node (ref "J10") (pin "P$37") (pinfunction "P$37_P$37") (pintype "bidirectional"))
      (node (ref "U4") (pin "93") (pinfunction "P1_12_93") (pintype "bidirectional"))
    )
    (net (code "92") (name "P1_13") (class "Default")
      (node (ref "J10") (pin "P$36") (pinfunction "P$36_P$36") (pintype "bidirectional"))
      (node (ref "U4") (pin "94") (pinfunction "P1_13_94") (pintype "bidirectional"))
    )
    (net (code "93") (name "P1_14") (class "Default")
      (node (ref "J10") (pin "P$35") (pinfunction "P$35_P$35") (pintype "bidirectional"))
      (node (ref "U4") (pin "95") (pinfunction "P1_14_95") (pintype "bidirectional"))
    )
    (net (code "94") (name "P1_15") (class "Default")
      (node (ref "J10") (pin "P$34") (pinfunction "P$34_P$34") (pintype "bidirectional"))
      (node (ref "U4") (pin "96") (pinfunction "P1_15_96") (pintype "bidirectional"))
    )
    (net (code "95") (name "P2_00") (class "Default")
      (node (ref "J16") (pin "3") (pinfunction "3_3") (pintype "passive"))
      (node (ref "R3") (pin "P$2") (pinfunction "2_P$2") (pintype "passive"))
      (node (ref "U4") (pin "69") (pinfunction "P2_0(INPUT_ONLY)_69") (pintype "bidirectional"))
    )
    (net (code "96") (name "P2_01") (class "Default")
      (node (ref "J16") (pin "1") (pinfunction "1_1") (pintype "passive"))
      (node (ref "R2") (pin "P$2") (pinfunction "2_P$2") (pintype "passive"))
      (node (ref "U4") (pin "68") (pinfunction "P2_1/MD_68") (pintype "bidirectional"))
    )
    (net (code "97") (name "P3_03") (class "Default")
      (node (ref "J12") (pin "1") (pinfunction "1_1") (pintype "passive"))
      (node (ref "U4") (pin "85") (pinfunction "P3_3_85") (pintype "bidirectional"))
    )
    (net (code "98") (name "P3_04") (class "Default")
      (node (ref "J12") (pin "2") (pinfunction "2_2") (pintype "passive"))
      (node (ref "U4") (pin "82") (pinfunction "P3_4_82") (pintype "bidirectional"))
    )
    (net (code "99") (name "P3_05") (class "Default")
      (node (ref "J12") (pin "3") (pinfunction "3_3") (pintype "passive"))
      (node (ref "U4") (pin "81") (pinfunction "P3_5_81") (pintype "bidirectional"))
    )
    (net (code "100") (name "P3_06") (class "Default")
      (node (ref "J12") (pin "4") (pinfunction "4_4") (pintype "passive"))
      (node (ref "U4") (pin "80") (pinfunction "P3_6_80") (pintype "bidirectional"))
    )
    (net (code "101") (name "P3_07") (class "Default")
      (node (ref "J12") (pin "5") (pinfunction "5_5") (pintype "passive"))
      (node (ref "U4") (pin "79") (pinfunction "P3_7_79") (pintype "bidirectional"))
    )
    (net (code "102") (name "P3_09") (class "Default")
      (node (ref "J12") (pin "6") (pinfunction "6_6") (pintype "passive"))
      (node (ref "U4") (pin "77") (pinfunction "P3_9_77") (pintype "bidirectional"))
    )
    (net (code "103") (name "P3_10") (class "Default")
      (node (ref "J12") (pin "7") (pinfunction "7_7") (pintype "passive"))
      (node (ref "U4") (pin "76") (pinfunction "P3_10_76") (pintype "bidirectional"))
    )
    (net (code "104") (name "P3_11") (class "Default")
      (node (ref "J12") (pin "8") (pinfunction "8_8") (pintype "passive"))
      (node (ref "U4") (pin "75") (pinfunction "P3_11_75") (pintype "bidirectional"))
    )
    (net (code "105") (name "P3_12") (class "Default")
      (node (ref "J12") (pin "9") (pinfunction "9_9") (pintype "passive"))
      (node (ref "U4") (pin "74") (pinfunction "P3_12_74") (pintype "bidirectional"))
    )
    (net (code "106") (name "P5_11") (class "Default")
      (node (ref "J7") (pin "7") (pinfunction "7_7") (pintype "passive"))
      (node (ref "U4") (pin "176") (pinfunction "P5_11_176") (pintype "bidirectional"))
    )
    (net (code "107") (name "P5_12") (class "Default")
      (node (ref "J7") (pin "8") (pinfunction "8_8") (pintype "passive"))
      (node (ref "U4") (pin "175") (pinfunction "P5_12_175") (pintype "bidirectional"))
    )
    (net (code "108") (name "P5_13") (class "Default")
      (node (ref "J7") (pin "5") (pinfunction "5_5") (pintype "passive"))
      (node (ref "U4") (pin "174") (pinfunction "P5_13_174") (pintype "bidirectional"))
    )
    (net (code "109") (name "P6_00") (class "Default")
      (node (ref "J10") (pin "P$13") (pinfunction "P$13_P$13") (pintype "bidirectional"))
      (node (ref "U4") (pin "122") (pinfunction "P6_0_122") (pintype "bidirectional"))
    )
    (net (code "110") (name "P6_01") (class "Default")
      (node (ref "J10") (pin "P$14") (pinfunction "P$14_P$14") (pintype "bidirectional"))
      (node (ref "U4") (pin "121") (pinfunction "P6_1_121") (pintype "bidirectional"))
    )
    (net (code "111") (name "P6_02") (class "Default")
      (node (ref "J10") (pin "P$15") (pinfunction "P$15_P$15") (pintype "bidirectional"))
      (node (ref "U4") (pin "120") (pinfunction "P6_2_120") (pintype "bidirectional"))
    )
    (net (code "112") (name "P6_03") (class "Default")
      (node (ref "J10") (pin "P$16") (pinfunction "P$16_P$16") (pintype "bidirectional"))
      (node (ref "U4") (pin "119") (pinfunction "P6_3_119") (pintype "bidirectional"))
    )
    (net (code "113") (name "P6_04") (class "Default")
      (node (ref "J10") (pin "P$17") (pinfunction "P$17_P$17") (pintype "bidirectional"))
      (node (ref "U4") (pin "118") (pinfunction "P6_4_118") (pintype "bidirectional"))
    )
    (net (code "114") (name "P6_05") (class "Default")
      (node (ref "J10") (pin "P$18") (pinfunction "P$18_P$18") (pintype "bidirectional"))
      (node (ref "U4") (pin "117") (pinfunction "P6_5_117") (pintype "bidirectional"))
    )
    (net (code "115") (name "P6_06") (class "Default")
      (node (ref "J10") (pin "P$19") (pinfunction "P$19_P$19") (pintype "bidirectional"))
      (node (ref "U4") (pin "116") (pinfunction "P6_6_116") (pintype "bidirectional"))
    )
    (net (code "116") (name "P6_07") (class "Default")
      (node (ref "J10") (pin "P$20") (pinfunction "P$20_P$20") (pintype "bidirectional"))
      (node (ref "U4") (pin "115") (pinfunction "P6_7_115") (pintype "bidirectional"))
    )
    (net (code "117") (name "P6_08") (class "Default")
      (node (ref "J10") (pin "P$33") (pinfunction "P$33_P$33") (pintype "bidirectional"))
      (node (ref "U4") (pin "99") (pinfunction "P6_8_99") (pintype "bidirectional"))
    )
    (net (code "118") (name "P6_09") (class "Default")
      (node (ref "J10") (pin "P$32") (pinfunction "P$32_P$32") (pintype "bidirectional"))
      (node (ref "U4") (pin "100") (pinfunction "P6_9_100") (pintype "bidirectional"))
    )
    (net (code "119") (name "P6_10") (class "Default")
      (node (ref "J10") (pin "P$31") (pinfunction "P$31_P$31") (pintype "bidirectional"))
      (node (ref "U4") (pin "101") (pinfunction "P6_10_101") (pintype "bidirectional"))
    )
    (net (code "120") (name "P6_11") (class "Default")
      (node (ref "J10") (pin "P$30") (pinfunction "P$30_P$30") (pintype "bidirectional"))
      (node (ref "U4") (pin "102") (pinfunction "P6_11_102") (pintype "bidirectional"))
    )
    (net (code "121") (name "P6_12") (class "Default")
      (node (ref "J10") (pin "P$29") (pinfunction "P$29_P$29") (pintype "bidirectional"))
      (node (ref "U4") (pin "103") (pinfunction "P6_12_103") (pintype "bidirectional"))
    )
    (net (code "122") (name "P6_13") (class "Default")
      (node (ref "J10") (pin "P$28") (pinfunction "P$28_P$28") (pintype "bidirectional"))
      (node (ref "U4") (pin "104") (pinfunction "P6_13_104") (pintype "bidirectional"))
    )
    (net (code "123") (name "P6_14") (class "Default")
      (node (ref "J10") (pin "P$27") (pinfunction "P$27_P$27") (pintype "bidirectional"))
      (node (ref "U4") (pin "105") (pinfunction "P6_14_105") (pintype "bidirectional"))
    )
    (net (code "124") (name "P6_15") (class "Default")
      (node (ref "J10") (pin "P$26") (pinfunction "P$26_P$26") (pintype "bidirectional"))
      (node (ref "U4") (pin "106") (pinfunction "P6_15_106") (pintype "bidirectional"))
    )
    (net (code "125") (name "P7_06") (class "Default")
      (node (ref "U4") (pin "14") (pinfunction "P7_6_14") (pintype "bidirectional"))
    )
    (net (code "126") (name "P7_07") (class "Default")
      (node (ref "U4") (pin "15") (pinfunction "P7_7_15") (pintype "bidirectional"))
    )
    (net (code "127") (name "P8_00") (class "Default")
      (node (ref "J10") (pin "P$4") (pinfunction "P$4_P$4") (pintype "bidirectional"))
      (node (ref "U4") (pin "133") (pinfunction "P8_0_133") (pintype "bidirectional"))
    )
    (net (code "128") (name "P8_01") (class "Default")
      (node (ref "J10") (pin "P$3") (pinfunction "P$3_P$3") (pintype "bidirectional"))
      (node (ref "U4") (pin "134") (pinfunction "P8_1_134") (pintype "bidirectional"))
    )
    (net (code "129") (name "P8_02") (class "Default")
      (node (ref "J10") (pin "P$2") (pinfunction "P$2_P$2") (pintype "bidirectional"))
      (node (ref "U4") (pin "135") (pinfunction "P8_2_135") (pintype "bidirectional"))
    )
    (net (code "130") (name "P8_03") (class "Default")
      (node (ref "J8") (pin "2") (pinfunction "2_2") (pintype "passive"))
      (node (ref "U4") (pin "136") (pinfunction "P8_3_136") (pintype "bidirectional"))
    )
    (net (code "131") (name "P8_04") (class "Default")
      (node (ref "J8") (pin "1") (pinfunction "1_1") (pintype "passive"))
      (node (ref "U4") (pin "137") (pinfunction "P8_4_137") (pintype "bidirectional"))
    )
    (net (code "132") (name "P8_05") (class "Default")
      (node (ref "J7") (pin "6") (pinfunction "6_6") (pintype "passive"))
      (node (ref "U4") (pin "173") (pinfunction "P8_5_173") (pintype "bidirectional"))
    )
    (net (code "133") (name "P9_05") (class "Default")
      (node (ref "J12") (pin "10") (pinfunction "10_10") (pintype "passive"))
      (node (ref "U4") (pin "73") (pinfunction "P9_5_73") (pintype "bidirectional"))
    )
    (net (code "134") (name "P9_06") (class "Default")
      (node (ref "J16") (pin "9") (pinfunction "9_9") (pintype "passive"))
      (node (ref "R10") (pin "P$2") (pinfunction "2_P$2") (pintype "passive"))
      (node (ref "U4") (pin "72") (pinfunction "P9_6_72") (pintype "bidirectional"))
    )
    (net (code "135") (name "P9_07") (class "Default")
      (node (ref "J16") (pin "7") (pinfunction "7_7") (pintype "passive"))
      (node (ref "R9") (pin "P$2") (pinfunction "2_P$2") (pintype "passive"))
      (node (ref "U4") (pin "71") (pinfunction "P9_7_71") (pintype "bidirectional"))
    )
    (net (code "136") (name "P9_08") (class "Default")
      (node (ref "J16") (pin "5") (pinfunction "5_5") (pintype "passive"))
      (node (ref "R8") (pin "P$2") (pinfunction "2_P$2") (pintype "passive"))
      (node (ref "U4") (pin "70") (pinfunction "P9_8_70") (pintype "bidirectional"))
    )
    (net (code "137") (name "PA_00") (class "Default")
      (node (ref "J10") (pin "P$21") (pinfunction "P$21_P$21") (pintype "bidirectional"))
      (node (ref "U4") (pin "114") (pinfunction "PA_0_114") (pintype "bidirectional"))
    )
    (net (code "138") (name "PA_01") (class "Default")
      (node (ref "J10") (pin "P$22") (pinfunction "P$22_P$22") (pintype "bidirectional"))
      (node (ref "U4") (pin "113") (pinfunction "PA_1_113") (pintype "bidirectional"))
    )
    (net (code "139") (name "PA_08") (class "Default")
      (node (ref "J10") (pin "P$25") (pinfunction "P$25_P$25") (pintype "bidirectional"))
      (node (ref "U4") (pin "107") (pinfunction "PA_8_107") (pintype "bidirectional"))
    )
    (net (code "140") (name "PA_09") (class "Default")
      (node (ref "J10") (pin "P$24") (pinfunction "P$24_P$24") (pintype "bidirectional"))
      (node (ref "U4") (pin "108") (pinfunction "PA_9_108") (pintype "bidirectional"))
    )
    (net (code "141") (name "PA_10") (class "Default")
      (node (ref "J10") (pin "P$23") (pinfunction "P$23_P$23") (pintype "bidirectional"))
      (node (ref "U4") (pin "109") (pinfunction "PA_10_109") (pintype "bidirectional"))
    )
    (net (code "142") (name "R51") (class "Default")
      (node (ref "J4") (pin "12") (pinfunction "YHI_12") (pintype "bidirectional"))
      (node (ref "R23") (pin "P$1") (pinfunction "1_P$1") (pintype "passive"))
    )
    (net (code "143") (name "R52") (class "Default")
      (node (ref "J4") (pin "9") (pinfunction "GHI_9") (pintype "bidirectional"))
      (node (ref "R24") (pin "P$1") (pinfunction "1_P$1") (pintype "passive"))
    )
    (net (code "144") (name "RELAY_0") (class "Default")
      (node (ref "RYS6") (pin "P$1") (pinfunction "1_P$1") (pintype "passive"))
      (node (ref "U4") (pin "59") (pinfunction "P9_1_59") (pintype "bidirectional"))
    )
    (net (code "145") (name "RELAY_1") (class "Default")
      (node (ref "RZS3") (pin "P$1") (pinfunction "1_P$1") (pintype "passive"))
      (node (ref "U4") (pin "58") (pinfunction "P9_0_58") (pintype "bidirectional"))
    )
    (net (code "146") (name "RELAY_2") (class "Default")
      (node (ref "RYS5") (pin "P$1") (pinfunction "1_P$1") (pintype "passive"))
      (node (ref "U4") (pin "57") (pinfunction "P3_15_57") (pintype "bidirectional"))
    )
    (net (code "147") (name "RELAY_3") (class "Default")
      (node (ref "RXS3") (pin "P$1") (pinfunction "1_P$1") (pintype "passive"))
      (node (ref "U4") (pin "56") (pinfunction "P3_14_56") (pintype "bidirectional"))
    )
    (net (code "148") (name "RELAY_4") (class "Default")
      (node (ref "RYS16") (pin "P$1") (pinfunction "1_P$1") (pintype "passive"))
      (node (ref "U4") (pin "55") (pinfunction "P3_13_55") (pintype "bidirectional"))
    )
    (net (code "149") (name "RELAY_5") (class "Default")
      (node (ref "RZS8") (pin "P$1") (pinfunction "1_P$1") (pintype "passive"))
      (node (ref "U4") (pin "52") (pinfunction "P2_4_52") (pintype "bidirectional"))
    )
    (net (code "150") (name "RELAY_6") (class "Default")
      (node (ref "RYS15") (pin "P$1") (pinfunction "1_P$1") (pintype "passive"))
      (node (ref "U4") (pin "51") (pinfunction "P2_5_51") (pintype "bidirectional"))
    )
    (net (code "151") (name "RELAY_7") (class "Default")
      (node (ref "RXS8") (pin "P$1") (pinfunction "1_P$1") (pintype "passive"))
      (node (ref "U4") (pin "50") (pinfunction "P2_6_50") (pintype "bidirectional"))
    )
    (net (code "152") (name "RESET") (class "Default")
      (node (ref "C57") (pin "P$1") (pinfunction "1_P$1") (pintype "passive"))
      (node (ref "J11") (pin "9") (pinfunction "9_9") (pintype "passive"))
      (node (ref "R18") (pin "P$1") (pinfunction "1_P$1") (pintype "passive"))
      (node (ref "U4") (pin "67") (pinfunction "RES#_67") (pintype "bidirectional"))
    )
    (net (code "153") (name "REXT") (class "Default")
      (node (ref "C47") (pin "P$1") (pinfunction "1_P$1") (pintype "passive"))
      (node (ref "R25") (pin "P$2") (pinfunction "2_P$2") (pintype "passive"))
      (node (ref "U3") (pin "9") (pinfunction "REXT_9") (pintype "input"))
    )
    (net (code "154") (name "RXD0") (class "Default")
      (node (ref "R31") (pin "P$2") (pinfunction "2_P$2") (pintype "passive"))
      (node (ref "U3") (pin "13") (pinfunction "RXD0_13") (pintype "bidirectional"))
    )
    (net (code "155") (name "RXD1") (class "Default")
      (node (ref "R30") (pin "P$2") (pinfunction "2_P$2") (pintype "passive"))
      (node (ref "U3") (pin "12") (pinfunction "RXD1_12") (pintype "bidirectional"))
    )
    (net (code "156") (name "RXER") (class "Default")
      (node (ref "R32") (pin "P$2") (pinfunction "2_P$2") (pintype "passive"))
      (node (ref "U3") (pin "17") (pinfunction "RXER_17") (pintype "bidirectional"))
    )
    (net (code "157") (name "RXM") (class "Default")
      (node (ref "J4") (pin "6") (pinfunction "RD-_6") (pintype "bidirectional"))
      (node (ref "U3") (pin "3") (pinfunction "RXM_3") (pintype "bidirectional"))
    )
    (net (code "158") (name "RXP") (class "Default")
      (node (ref "J4") (pin "3") (pinfunction "RD+_3") (pintype "bidirectional"))
      (node (ref "U3") (pin "4") (pinfunction "RXP_4") (pintype "bidirectional"))
    )
    (net (code "159") (name "SD1_CD") (class "Default")
      (node (ref "J9") (pin "10") (pinfunction "CD_SWITCH2_10") (pintype "bidirectional"))
      (node (ref "U4") (pin "146") (pinfunction "P5_6/AN019_146") (pintype "bidirectional"))
    )
    (net (code "160") (name "SD1_CLK") (class "Default")
      (node (ref "J9") (pin "5") (pinfunction "CLOCK_5") (pintype "bidirectional"))
      (node (ref "U4") (pin "140") (pinfunction "P5_0/AN016_140") (pintype "bidirectional"))
    )
    (net (code "161") (name "SD1_CMD") (class "Default")
      (node (ref "J9") (pin "3") (pinfunction "COMMAND/RESPONSE_3") (pintype "bidirectional"))
      (node (ref "U4") (pin "141") (pinfunction "P5_1/AN116_141") (pintype "bidirectional"))
    )
    (net (code "162") (name "SD1_DAT0") (class "Default")
      (node (ref "J9") (pin "7") (pinfunction "DATA_LINE[BIT_0]_7") (pintype "bidirectional"))
      (node (ref "U4") (pin "142") (pinfunction "P5_2/AN017_142") (pintype "bidirectional"))
    )
    (net (code "163") (name "SD1_DAT1") (class "Default")
      (node (ref "J9") (pin "8") (pinfunction "DATA_LINE[BIT_1]_8") (pintype "bidirectional"))
      (node (ref "U4") (pin "143") (pinfunction "P5_3/AN117_143") (pintype "bidirectional"))
    )
    (net (code "164") (name "SD1_DAT2") (class "Default")
      (node (ref "J9") (pin "1") (pinfunction "DATA_LINE[BIT_2]_1") (pintype "bidirectional"))
      (node (ref "U4") (pin "144") (pinfunction "P5_4/AN018_144") (pintype "bidirectional"))
    )
    (net (code "165") (name "SD1_DAT3") (class "Default")
      (node (ref "J9") (pin "2") (pinfunction "CARD_DETECT/DATA_LINE[BIT_3]_2") (pintype "bidirectional"))
      (node (ref "U4") (pin "145") (pinfunction "P5_5/AN118_145") (pintype "bidirectional"))
    )
    (net (code "166") (name "SD1_WP") (class "Default")
      (node (ref "J9") (pin "9") (pinfunction "CD_SWITCH1_9") (pintype "bidirectional"))
      (node (ref "U4") (pin "147") (pinfunction "P5_7/AN119_147") (pintype "bidirectional"))
    )
    (net (code "167") (name "TCK") (class "Default")
      (node (ref "J11") (pin "7") (pinfunction "7_7") (pintype "passive"))
      (node (ref "U4") (pin "88") (pinfunction "P3_0_88") (pintype "bidirectional"))
    )
    (net (code "168") (name "TDI") (class "Default")
      (node (ref "J11") (pin "1") (pinfunction "1_1") (pintype "passive"))
      (node (ref "U4") (pin "91") (pinfunction "P1_10_91") (pintype "bidirectional"))
    )
    (net (code "169") (name "TDO") (class "Default")
      (node (ref "J11") (pin "3") (pinfunction "3_3") (pintype "passive"))
      (node (ref "U4") (pin "90") (pinfunction "P1_9_90") (pintype "bidirectional"))
    )
    (net (code "170") (name "TMS") (class "Default")
      (node (ref "J11") (pin "5") (pinfunction "5_5") (pintype "passive"))
      (node (ref "U4") (pin "89") (pinfunction "P1_8_89") (pintype "bidirectional"))
    )
    (net (code "171") (name "TXM") (class "Default")
      (node (ref "J4") (pin "2") (pinfunction "TD-_2") (pintype "bidirectional"))
      (node (ref "U3") (pin "5") (pinfunction "TXM_5") (pintype "bidirectional"))
    )
    (net (code "172") (name "TXP") (class "Default")
      (node (ref "J4") (pin "1") (pinfunction "TD+_1") (pintype "bidirectional"))
      (node (ref "U3") (pin "6") (pinfunction "TXP_6") (pintype "bidirectional"))
    )
    (net (code "173") (name "USBHS_FAULT") (class "Default")
      (node (ref "R12") (pin "P$1") (pinfunction "1_P$1") (pintype "passive"))
      (node (ref "U2") (pin "3") (pinfunction "FLG_3") (pintype "input"))
      (node (ref "U4") (pin "78") (pinfunction "P3_8_78") (pintype "bidirectional"))
    )
    (net (code "174") (name "USBHS_N") (class "Default")
      (node (ref "J3") (pin "D-") (pinfunction "D-_D-") (pintype "bidirectional"))
      (node (ref "U4") (pin "31") (pinfunction "USBHS_DM_31") (pintype "bidirectional"))
    )
    (net (code "175") (name "USBHS_P") (class "Default")
      (node (ref "J3") (pin "D+") (pinfunction "D+_D+") (pintype "bidirectional"))
      (node (ref "U4") (pin "32") (pinfunction "USBHS_DP_32") (pintype "bidirectional"))
    )
    (net (code "176") (name "USBHS_VBUS") (class "Default")
      (node (ref "C11") (pin "P$1") (pinfunction "1_P$1") (pintype "passive"))
      (node (ref "C15") (pin "1") (pinfunction "1_1") (pintype "passive"))
      (node (ref "J3") (pin "VBUS") (pinfunction "VBUS_VBUS") (pintype "power_in"))
      (node (ref "U2") (pin "5") (pinfunction "OUT_5") (pintype "input"))
      (node (ref "U4") (pin "17") (pinfunction "PB_1_17") (pintype "bidirectional"))
    )
    (net (code "177") (name "USBHS_VBUSEN") (class "Default")
      (node (ref "R1") (pin "P$1") (pinfunction "1_P$1") (pintype "passive"))
      (node (ref "U2") (pin "1") (pinfunction "EN_1") (pintype "input"))
    )
    (net (code "178") (name "USB_N") (class "Default")
      (node (ref "R5") (pin "P$1") (pinfunction "1_P$1") (pintype "passive"))
      (node (ref "U4") (pin "46") (pinfunction "USB_DM_46") (pintype "bidirectional"))
    )
    (net (code "179") (name "USB_P") (class "Default")
      (node (ref "R6") (pin "P$1") (pinfunction "1_P$1") (pintype "passive"))
      (node (ref "U4") (pin "47") (pinfunction "USB_DP_47") (pintype "bidirectional"))
    )
    (net (code "180") (name "USB_VBUS_B") (class "Default")
      (node (ref "R4") (pin "P$1") (pinfunction "1_P$1") (pintype "passive"))
      (node (ref "U4") (pin "44") (pinfunction "P4_7_44") (pintype "bidirectional"))
    )
    (net (code "181") (name "VCL_F(FLASH)") (class "Default")
      (node (ref "C36") (pin "P$2") (pinfunction "2_P$2") (pintype "passive"))
      (node (ref "U4") (pin "112") (pinfunction "VCL_F(FLASH)_112") (pintype "bidirectional"))
    )
    (net (code "182") (name "VDD") (class "Default")
      (node (ref "C10") (pin "P$2") (pinfunction "2_P$2") (pintype "passive"))
      (node (ref "C13") (pin "P$2") (pinfunction "2_P$2") (pintype "passive"))
      (node (ref "C14") (pin "P$2") (pinfunction "2_P$2") (pintype "passive"))
      (node (ref "C30") (pin "P$2") (pinfunction "2_P$2") (pintype "passive"))
      (node (ref "C32") (pin "P$1") (pinfunction "1_P$1") (pintype "passive"))
      (node (ref "C33") (pin "P$1") (pinfunction "1_P$1") (pintype "passive"))
      (node (ref "C34") (pin "P$1") (pinfunction "1_P$1") (pintype "passive"))
      (node (ref "C35") (pin "P$1") (pinfunction "1_P$1") (pintype "passive"))
      (node (ref "C48") (pin "1") (pinfunction "1_1") (pintype "passive"))
      (node (ref "C49") (pin "P$1") (pinfunction "1_P$1") (pintype "passive"))
      (node (ref "C54") (pin "P$2") (pinfunction "2_P$2") (pintype "passive"))
      (node (ref "C55") (pin "P$2") (pinfunction "2_P$2") (pintype "passive"))
      (node (ref "C56") (pin "P$2") (pinfunction "2_P$2") (pintype "passive"))
      (node (ref "C58") (pin "P$1") (pinfunction "1_P$1") (pintype "passive"))
      (node (ref "C59") (pin "P$1") (pinfunction "1_P$1") (pintype "passive"))
      (node (ref "C60") (pin "P$1") (pinfunction "1_P$1") (pintype "passive"))
      (node (ref "C61") (pin "P$2") (pinfunction "2_P$2") (pintype "passive"))
      (node (ref "FB2/2") (pin "1") (pinfunction "P$1_1") (pintype "bidirectional"))
      (node (ref "J11") (pin "2") (pinfunction "2_2") (pintype "passive"))
      (node (ref "J11") (pin "4") (pinfunction "4_4") (pintype "passive"))
      (node (ref "J9") (pin "4") (pinfunction "SUPPLY_VOLTAGE_4") (pintype "power_in"))
      (node (ref "L3") (pin "2") (pinfunction "P$2_2") (pintype "bidirectional"))
      (node (ref "R10") (pin "P$1") (pinfunction "1_P$1") (pintype "passive"))
      (node (ref "R11") (pin "P$1") (pinfunction "1_P$1") (pintype "passive"))
      (node (ref "R13") (pin "P$2") (pinfunction "2_P$2") (pintype "passive"))
      (node (ref "R14") (pin "P$1") (pinfunction "1_P$1") (pintype "passive"))
      (node (ref "R18") (pin "P$2") (pinfunction "2_P$2") (pintype "passive"))
      (node (ref "R2") (pin "P$1") (pinfunction "1_P$1") (pintype "passive"))
      (node (ref "R20") (pin "P$1") (pinfunction "1_P$1") (pintype "passive"))
      (node (ref "R21") (pin "P$1") (pinfunction "1_P$1") (pintype "passive"))
      (node (ref "R23") (pin "P$2") (pinfunction "2_P$2") (pintype "passive"))
      (node (ref "R24") (pin "P$2") (pinfunction "2_P$2") (pintype "passive"))
      (node (ref "R26") (pin "P$2") (pinfunction "2_P$2") (pintype "passive"))
      (node (ref "R27") (pin "P$2") (pinfunction "2_P$2") (pintype "passive"))
      (node (ref "R28") (pin "P$2") (pinfunction "2_P$2") (pintype "passive"))
      (node (ref "R29") (pin "P$2") (pinfunction "2_P$2") (pintype "passive"))
      (node (ref "R3") (pin "P$1") (pinfunction "1_P$1") (pintype "passive"))
      (node (ref "R8") (pin "P$1") (pinfunction "1_P$1") (pintype "passive"))
      (node (ref "R9") (pin "P$1") (pinfunction "1_P$1") (pintype "passive"))
      (node (ref "U3") (pin "14") (pinfunction "VDDIO_14") (pintype "power_in"))
      (node (ref "U4") (pin "110") (pinfunction "VCC(IO)5_110") (pintype "bidirectional"))
      (node (ref "U4") (pin "123") (pinfunction "VCC(IO)6_123") (pintype "bidirectional"))
      (node (ref "U4") (pin "138") (pinfunction "VCC(IO)7_138") (pintype "bidirectional"))
      (node (ref "U4") (pin "149") (pinfunction "VCC(IO)8_149") (pintype "bidirectional"))
      (node (ref "U4") (pin "155") (pinfunction "AVCC0_155") (pintype "bidirectional"))
      (node (ref "U4") (pin "171") (pinfunction "VCC(IO)9_171") (pintype "bidirectional"))
      (node (ref "U4") (pin "25") (pinfunction "VCC1_25") (pintype "bidirectional"))
      (node (ref "U4") (pin "26") (pinfunction "AVCC_SUBHS_26") (pintype "bidirectional"))
      (node (ref "U4") (pin "34") (pinfunction "VCC_USBHS_34") (pintype "bidirectional"))
      (node (ref "U4") (pin "48") (pinfunction "VCC_USB_48") (pintype "bidirectional"))
      (node (ref "U4") (pin "61") (pinfunction "VCC(IO)2_61") (pintype "bidirectional"))
      (node (ref "U4") (pin "84") (pinfunction "VCC(IO)3_84") (pintype "bidirectional"))
      (node (ref "U4") (pin "97") (pinfunction "VCC(IO)4_97") (pintype "bidirectional"))
    )
    (net (code "183") (name "VDD5") (class "Default")
      (node (ref "C5") (pin "P$1") (pinfunction "1_P$1") (pintype "passive"))
      (node (ref "C8") (pin "P$1") (pinfunction "1_P$1") (pintype "passive"))
      (node (ref "J1") (pin "5") (pinfunction "5_5") (pintype "passive"))
      (node (ref "J1") (pin "6") (pinfunction "6_6") (pintype "passive"))
      (node (ref "R1") (pin "P$2") (pinfunction "2_P$2") (pintype "passive"))
      (node (ref "R12") (pin "P$2") (pinfunction "2_P$2") (pintype "passive"))
      (node (ref "U2") (pin "4") (pinfunction "VIN_4") (pintype "input"))
    )
    (net (code "184") (name "VDD12") (class "Default")
      (node (ref "J1") (pin "7") (pinfunction "7_7") (pintype "passive"))
      (node (ref "J1") (pin "8") (pinfunction "8_8") (pintype "passive"))
    )
    (net (code "185") (name "VDDIN") (class "Default")
      (node (ref "J1") (pin "3") (pinfunction "3_3") (pintype "passive"))
      (node (ref "J1") (pin "4") (pinfunction "4_4") (pintype "passive"))
      (node (ref "L3") (pin "1") (pinfunction "P$1_1") (pintype "bidirectional"))
    )
    (net (code "186") (name "VDD_1.2") (class "Default")
      (node (ref "C45") (pin "P$1") (pinfunction "1_P$1") (pintype "passive"))
      (node (ref "C46") (pin "P$1") (pinfunction "1_P$1") (pintype "passive"))
      (node (ref "U3") (pin "1") (pinfunction "VDD_1.2_1") (pintype "power_in"))
    )
    (net (code "187") (name "XCIN") (class "Default")
      (node (ref "C50") (pin "P$1") (pinfunction "1_P$1") (pintype "passive"))
      (node (ref "U4") (pin "20") (pinfunction "XCIN_20") (pintype "bidirectional"))
      (node (ref "X3") (pin "P$1") (pinfunction "P$1_P$1") (pintype "bidirectional"))
    )
    (net (code "188") (name "XCOUT") (class "Default")
      (node (ref "C51") (pin "P$1") (pinfunction "1_P$1") (pintype "passive"))
      (node (ref "U4") (pin "21") (pinfunction "XCOUT_21") (pintype "bidirectional"))
      (node (ref "X3") (pin "P$2") (pinfunction "P$2_P$2") (pintype "bidirectional"))
    )
    (net (code "189") (name "XII") (class "Default")
      (node (ref "C42") (pin "P$1") (pinfunction "1_P$1") (pintype "passive"))
      (node (ref "U$3") (pin "1") (pinfunction "1_1") (pintype "bidirectional"))
      (node (ref "U3") (pin "8") (pinfunction "XI_8") (pintype "input"))
    )
    (net (code "190") (name "XOO") (class "Default")
      (node (ref "C41") (pin "P$1") (pinfunction "1_P$1") (pintype "passive"))
      (node (ref "U$3") (pin "3") (pinfunction "3_3") (pintype "bidirectional"))
      (node (ref "U3") (pin "7") (pinfunction "XO_7") (pintype "output"))
    )
    (net (code "191") (name "XTAL1") (class "Default")
      (node (ref "C52") (pin "P$1") (pinfunction "1_P$1") (pintype "passive"))
      (node (ref "U4") (pin "23") (pinfunction "P2_13/XTAL_23") (pintype "bidirectional"))
      (node (ref "X4") (pin "1") (pinfunction "1_1") (pintype "bidirectional"))
    )
    (net (code "192") (name "XTAL2") (class "Default")
      (node (ref "C53") (pin "P$1") (pinfunction "1_P$1") (pintype "passive"))
      (node (ref "U4") (pin "24") (pinfunction "P2_12/EXTAL_24") (pintype "bidirectional"))
      (node (ref "X4") (pin "3") (pinfunction "3_3") (pintype "bidirectional"))
    )
    (net (code "193") (name "unconnected-(U4-VBAT-Pad18)") (class "Default")
      (node (ref "U4") (pin "18") (pinfunction "VBAT_18") (pintype "bidirectional"))
    )
    (net (code "194") (name "unconnected-(U4-VREFH-Pad154)") (class "Default")
      (node (ref "U4") (pin "154") (pinfunction "VREFH_154") (pintype "bidirectional"))
    )
    (net (code "195") (name "unconnected-(U4-VREFH0-Pad158)") (class "Default")
      (node (ref "U4") (pin "158") (pinfunction "VREFH0_158") (pintype "bidirectional"))
    )
    (net (code "196") (name "unconnected-(U4-VREFL-Pad153)") (class "Default")
      (node (ref "U4") (pin "153") (pinfunction "VREFL_153") (pintype "bidirectional"))
    )
    (net (code "197") (name "unconnected-(U4-VREFL0-Pad157)") (class "Default")
      (node (ref "U4") (pin "157") (pinfunction "VREFL0_157") (pintype "bidirectional"))
    )
  )
)
